# AFE_32.net
KiCad netlist of a schematic drawn in Altium Designer
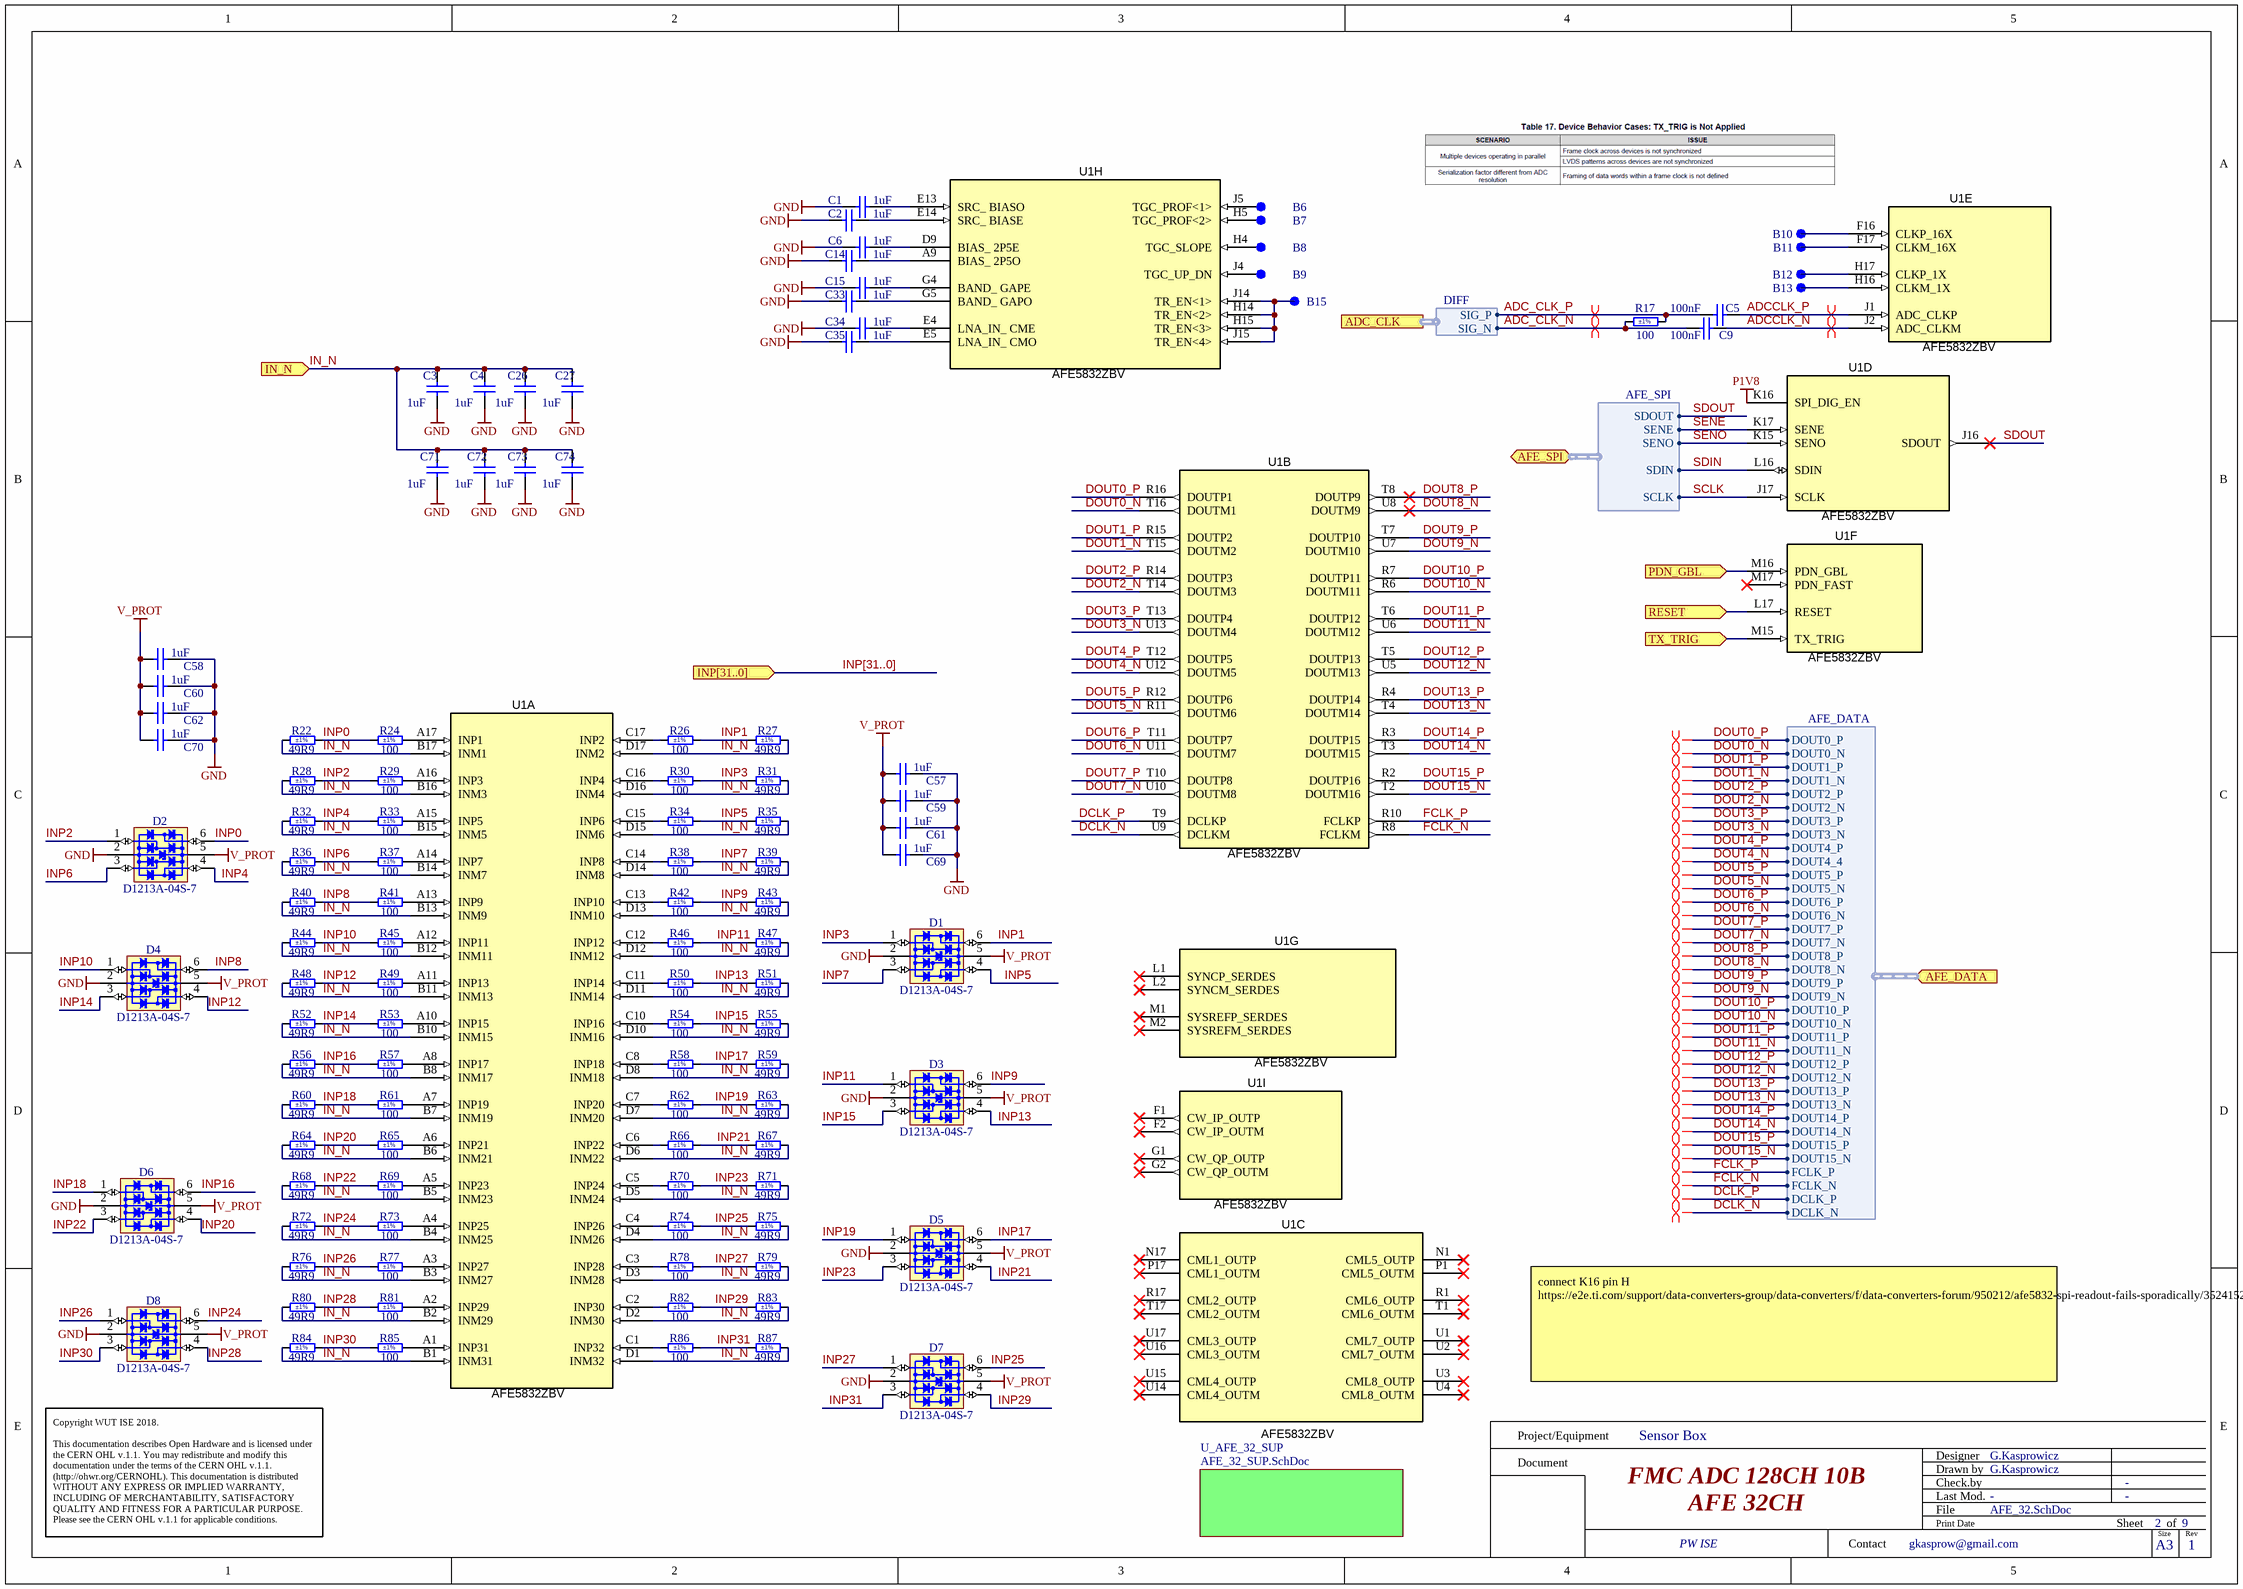
[diagram p0: AFE_32.SchDoc]

(export (version "E")
  (design (tool "Eeschema 10.0.6"))
  (components
    (comp (ref "B6")
      (value "SMD Pad")
      (footprint "C75")
      (description "Through Hole Pad")
      (fields (field (name "PART NUMBER") "SMD_PAD_D0.75MM") (field (name "AUTHOR") "CERN DEM BC"))
      (libsource (lib "Eletro-mechanical") (part "Single SMD Pad (Round)"))
    )
    (comp (ref "B7")
      (value "SMD Pad")
      (footprint "C75")
      (description "Through Hole Pad")
      (fields (field (name "PART NUMBER") "SMD_PAD_D0.75MM") (field (name "AUTHOR") "CERN DEM BC"))
      (libsource (lib "Eletro-mechanical") (part "Single SMD Pad (Round)"))
    )
    (comp (ref "B8")
      (value "SMD Pad")
      (footprint "C75")
      (description "Through Hole Pad")
      (fields (field (name "PART NUMBER") "SMD_PAD_D0.75MM") (field (name "AUTHOR") "CERN DEM BC"))
      (libsource (lib "Eletro-mechanical") (part "Single SMD Pad (Round)"))
    )
    (comp (ref "B9")
      (value "SMD Pad")
      (footprint "C75")
      (description "Through Hole Pad")
      (fields (field (name "PART NUMBER") "SMD_PAD_D0.75MM") (field (name "AUTHOR") "CERN DEM BC"))
      (libsource (lib "Eletro-mechanical") (part "Single SMD Pad (Round)"))
    )
    (comp (ref "B10")
      (value "SMD Pad")
      (footprint "C75")
      (description "Through Hole Pad")
      (fields (field (name "PART NUMBER") "SMD_PAD_D0.75MM") (field (name "AUTHOR") "CERN DEM BC"))
      (libsource (lib "Eletro-mechanical") (part "Single SMD Pad (Round)"))
    )
    (comp (ref "B11")
      (value "SMD Pad")
      (footprint "C75")
      (description "Through Hole Pad")
      (fields (field (name "PART NUMBER") "SMD_PAD_D0.75MM") (field (name "AUTHOR") "CERN DEM BC"))
      (libsource (lib "Eletro-mechanical") (part "Single SMD Pad (Round)"))
    )
    (comp (ref "B12")
      (value "SMD Pad")
      (footprint "C75")
      (description "Through Hole Pad")
      (fields (field (name "PART NUMBER") "SMD_PAD_D0.75MM") (field (name "AUTHOR") "CERN DEM BC"))
      (libsource (lib "Eletro-mechanical") (part "Single SMD Pad (Round)"))
    )
    (comp (ref "B13")
      (value "SMD Pad")
      (footprint "C75")
      (description "Through Hole Pad")
      (fields (field (name "PART NUMBER") "SMD_PAD_D0.75MM") (field (name "AUTHOR") "CERN DEM BC"))
      (libsource (lib "Eletro-mechanical") (part "Single SMD Pad (Round)"))
    )
    (comp (ref "B15")
      (value "SMD Pad")
      (footprint "C75")
      (description "Through Hole Pad")
      (fields (field (name "PART NUMBER") "SMD_PAD_D0.75MM") (field (name "AUTHOR") "CERN DEM BC"))
      (libsource (lib "Eletro-mechanical") (part "Single SMD Pad (Round)"))
    )
    (comp (ref "C1")
      (value "1uF")
      (footprint "CAPC1005X55N")
      (description "Non-polarised capacitor")
      (fields
        (field (name "PART NUMBER") "CC0402_1UF_25V_10%_X5R")
        (field (name "VOLTAGE") "25V")
        (field (name "AUTHOR") "CERN DEM BC")
      )
      (libsource (lib "Capacitors") (part "Capacitor - non polarized"))
    )
    (comp (ref "C2")
      (value "1uF")
      (footprint "CAPC1005X55N")
      (description "Non-polarised capacitor")
      (fields
        (field (name "PART NUMBER") "CC0402_1UF_25V_10%_X5R")
        (field (name "VOLTAGE") "25V")
        (field (name "AUTHOR") "CERN DEM BC")
      )
      (libsource (lib "Capacitors") (part "Capacitor - non polarized"))
    )
    (comp (ref "C3")
      (value "1uF")
      (footprint "CAPC1005X55N")
      (description "Non-polarised capacitor")
      (fields
        (field (name "PART NUMBER") "CC0402_1UF_25V_10%_X5R")
        (field (name "VOLTAGE") "25V")
        (field (name "AUTHOR") "CERN DEM BC")
      )
      (libsource (lib "Capacitors") (part "Capacitor - non polarized"))
    )
    (comp (ref "C4")
      (value "1uF")
      (footprint "CAPC1005X55N")
      (description "Non-polarised capacitor")
      (fields
        (field (name "PART NUMBER") "CC0402_1UF_25V_10%_X5R")
        (field (name "VOLTAGE") "25V")
        (field (name "AUTHOR") "CERN DEM BC")
      )
      (libsource (lib "Capacitors") (part "Capacitor - non polarized"))
    )
    (comp (ref "C5")
      (value "100nF")
      (footprint "CAPC0603X33N")
      (description "Non-polarised capacitor")
      (fields
        (field (name "PART NUMBER") "CC0201_100NF_6.3V_10%_X5R")
        (field (name "VOLTAGE") "6.3V")
        (field (name "AUTHOR") "CERN DEM JLC")
      )
      (libsource (lib "Capacitors") (part "Capacitor - non polarized"))
    )
    (comp (ref "C6")
      (value "1uF")
      (footprint "CAPC1005X55N")
      (description "Non-polarised capacitor")
      (fields
        (field (name "PART NUMBER") "CC0402_1UF_25V_10%_X5R")
        (field (name "VOLTAGE") "25V")
        (field (name "AUTHOR") "CERN DEM BC")
      )
      (libsource (lib "Capacitors") (part "Capacitor - non polarized"))
    )
    (comp (ref "C9")
      (value "100nF")
      (footprint "CAPC0603X33N")
      (description "Non-polarised capacitor")
      (fields
        (field (name "PART NUMBER") "CC0201_100NF_6.3V_10%_X5R")
        (field (name "VOLTAGE") "6.3V")
        (field (name "AUTHOR") "CERN DEM JLC")
      )
      (libsource (lib "Capacitors") (part "Capacitor - non polarized"))
    )
    (comp (ref "C14")
      (value "1uF")
      (footprint "CAPC1005X55N")
      (description "Non-polarised capacitor")
      (fields
        (field (name "PART NUMBER") "CC0402_1UF_25V_10%_X5R")
        (field (name "VOLTAGE") "25V")
        (field (name "AUTHOR") "CERN DEM BC")
      )
      (libsource (lib "Capacitors") (part "Capacitor - non polarized"))
    )
    (comp (ref "C15")
      (value "1uF")
      (footprint "CAPC1005X55N")
      (description "Non-polarised capacitor")
      (fields
        (field (name "PART NUMBER") "CC0402_1UF_25V_10%_X5R")
        (field (name "VOLTAGE") "25V")
        (field (name "AUTHOR") "CERN DEM BC")
      )
      (libsource (lib "Capacitors") (part "Capacitor - non polarized"))
    )
    (comp (ref "C26")
      (value "1uF")
      (footprint "CAPC1005X55N")
      (description "Non-polarised capacitor")
      (fields
        (field (name "PART NUMBER") "CC0402_1UF_25V_10%_X5R")
        (field (name "VOLTAGE") "25V")
        (field (name "AUTHOR") "CERN DEM BC")
      )
      (libsource (lib "Capacitors") (part "Capacitor - non polarized"))
    )
    (comp (ref "C27")
      (value "1uF")
      (footprint "CAPC1005X55N")
      (description "Non-polarised capacitor")
      (fields
        (field (name "PART NUMBER") "CC0402_1UF_25V_10%_X5R")
        (field (name "VOLTAGE") "25V")
        (field (name "AUTHOR") "CERN DEM BC")
      )
      (libsource (lib "Capacitors") (part "Capacitor - non polarized"))
    )
    (comp (ref "C33")
      (value "1uF")
      (footprint "CAPC1005X55N")
      (description "Non-polarised capacitor")
      (fields
        (field (name "PART NUMBER") "CC0402_1UF_25V_10%_X5R")
        (field (name "VOLTAGE") "25V")
        (field (name "AUTHOR") "CERN DEM BC")
      )
      (libsource (lib "Capacitors") (part "Capacitor - non polarized"))
    )
    (comp (ref "C34")
      (value "1uF")
      (footprint "CAPC1005X55N")
      (description "Non-polarised capacitor")
      (fields
        (field (name "PART NUMBER") "CC0402_1UF_25V_10%_X5R")
        (field (name "VOLTAGE") "25V")
        (field (name "AUTHOR") "CERN DEM BC")
      )
      (libsource (lib "Capacitors") (part "Capacitor - non polarized"))
    )
    (comp (ref "C35")
      (value "1uF")
      (footprint "CAPC1005X55N")
      (description "Non-polarised capacitor")
      (fields
        (field (name "PART NUMBER") "CC0402_1UF_25V_10%_X5R")
        (field (name "VOLTAGE") "25V")
        (field (name "AUTHOR") "CERN DEM BC")
      )
      (libsource (lib "Capacitors") (part "Capacitor - non polarized"))
    )
    (comp (ref "C57")
      (value "1uF")
      (footprint "CAPC1005X55N")
      (description "Non-polarised capacitor")
      (fields
        (field (name "PART NUMBER") "CC0402_1UF_25V_10%_X5R")
        (field (name "VOLTAGE") "25V")
        (field (name "AUTHOR") "CERN DEM BC")
      )
      (libsource (lib "Capacitors") (part "Capacitor - non polarized"))
    )
    (comp (ref "C58")
      (value "1uF")
      (footprint "CAPC1005X55N")
      (description "Non-polarised capacitor")
      (fields
        (field (name "PART NUMBER") "CC0402_1UF_25V_10%_X5R")
        (field (name "VOLTAGE") "25V")
        (field (name "AUTHOR") "CERN DEM BC")
      )
      (libsource (lib "Capacitors") (part "Capacitor - non polarized"))
    )
    (comp (ref "C59")
      (value "1uF")
      (footprint "CAPC1005X55N")
      (description "Non-polarised capacitor")
      (fields
        (field (name "PART NUMBER") "CC0402_1UF_25V_10%_X5R")
        (field (name "VOLTAGE") "25V")
        (field (name "AUTHOR") "CERN DEM BC")
      )
      (libsource (lib "Capacitors") (part "Capacitor - non polarized"))
    )
    (comp (ref "C60")
      (value "1uF")
      (footprint "CAPC1005X55N")
      (description "Non-polarised capacitor")
      (fields
        (field (name "PART NUMBER") "CC0402_1UF_25V_10%_X5R")
        (field (name "VOLTAGE") "25V")
        (field (name "AUTHOR") "CERN DEM BC")
      )
      (libsource (lib "Capacitors") (part "Capacitor - non polarized"))
    )
    (comp (ref "C61")
      (value "1uF")
      (footprint "CAPC1005X55N")
      (description "Non-polarised capacitor")
      (fields
        (field (name "PART NUMBER") "CC0402_1UF_25V_10%_X5R")
        (field (name "VOLTAGE") "25V")
        (field (name "AUTHOR") "CERN DEM BC")
      )
      (libsource (lib "Capacitors") (part "Capacitor - non polarized"))
    )
    (comp (ref "C62")
      (value "1uF")
      (footprint "CAPC1005X55N")
      (description "Non-polarised capacitor")
      (fields
        (field (name "PART NUMBER") "CC0402_1UF_25V_10%_X5R")
        (field (name "VOLTAGE") "25V")
        (field (name "AUTHOR") "CERN DEM BC")
      )
      (libsource (lib "Capacitors") (part "Capacitor - non polarized"))
    )
    (comp (ref "C69")
      (value "1uF")
      (footprint "CAPC1005X55N")
      (description "Non-polarised capacitor")
      (fields
        (field (name "PART NUMBER") "CC0402_1UF_25V_10%_X5R")
        (field (name "VOLTAGE") "25V")
        (field (name "AUTHOR") "CERN DEM BC")
      )
      (libsource (lib "Capacitors") (part "Capacitor - non polarized"))
    )
    (comp (ref "C70")
      (value "1uF")
      (footprint "CAPC1005X55N")
      (description "Non-polarised capacitor")
      (fields
        (field (name "PART NUMBER") "CC0402_1UF_25V_10%_X5R")
        (field (name "VOLTAGE") "25V")
        (field (name "AUTHOR") "CERN DEM BC")
      )
      (libsource (lib "Capacitors") (part "Capacitor - non polarized"))
    )
    (comp (ref "C71")
      (value "1uF")
      (footprint "CAPC1005X55N")
      (description "Non-polarised capacitor")
      (fields
        (field (name "PART NUMBER") "CC0402_1UF_25V_10%_X5R")
        (field (name "VOLTAGE") "25V")
        (field (name "AUTHOR") "CERN DEM BC")
      )
      (libsource (lib "Capacitors") (part "Capacitor - non polarized"))
    )
    (comp (ref "C72")
      (value "1uF")
      (footprint "CAPC1005X55N")
      (description "Non-polarised capacitor")
      (fields
        (field (name "PART NUMBER") "CC0402_1UF_25V_10%_X5R")
        (field (name "VOLTAGE") "25V")
        (field (name "AUTHOR") "CERN DEM BC")
      )
      (libsource (lib "Capacitors") (part "Capacitor - non polarized"))
    )
    (comp (ref "C73")
      (value "1uF")
      (footprint "CAPC1005X55N")
      (description "Non-polarised capacitor")
      (fields
        (field (name "PART NUMBER") "CC0402_1UF_25V_10%_X5R")
        (field (name "VOLTAGE") "25V")
        (field (name "AUTHOR") "CERN DEM BC")
      )
      (libsource (lib "Capacitors") (part "Capacitor - non polarized"))
    )
    (comp (ref "C74")
      (value "1uF")
      (footprint "CAPC1005X55N")
      (description "Non-polarised capacitor")
      (fields
        (field (name "PART NUMBER") "CC0402_1UF_25V_10%_X5R")
        (field (name "VOLTAGE") "25V")
        (field (name "AUTHOR") "CERN DEM BC")
      )
      (libsource (lib "Capacitors") (part "Capacitor - non polarized"))
    )
    (comp (ref "D1")
      (value "D1213A-04S-7")
      (footprint "SOT65P210X110-6N")
      (description "Integrated Quad Ultra-Low Capacitance ESD Protection")
      (fields (field (name "MANUFACTURER") "DIODES") (field (name "AUTHOR") "GK"))
      (libsource (lib "Diodes") (part "D_TVS_D1213A-04S-7"))
    )
    (comp (ref "D2")
      (value "D1213A-04S-7")
      (footprint "SOT65P210X110-6N")
      (description "Integrated Quad Ultra-Low Capacitance ESD Protection")
      (fields (field (name "MANUFACTURER") "DIODES") (field (name "AUTHOR") "GK"))
      (libsource (lib "Diodes") (part "D_TVS_D1213A-04S-7"))
    )
    (comp (ref "D3")
      (value "D1213A-04S-7")
      (footprint "SOT65P210X110-6N")
      (description "Integrated Quad Ultra-Low Capacitance ESD Protection")
      (fields (field (name "MANUFACTURER") "DIODES") (field (name "AUTHOR") "GK"))
      (libsource (lib "Diodes") (part "D_TVS_D1213A-04S-7"))
    )
    (comp (ref "D4")
      (value "D1213A-04S-7")
      (footprint "SOT65P210X110-6N")
      (description "Integrated Quad Ultra-Low Capacitance ESD Protection")
      (fields (field (name "MANUFACTURER") "DIODES") (field (name "AUTHOR") "GK"))
      (libsource (lib "Diodes") (part "D_TVS_D1213A-04S-7"))
    )
    (comp (ref "D5")
      (value "D1213A-04S-7")
      (footprint "SOT65P210X110-6N")
      (description "Integrated Quad Ultra-Low Capacitance ESD Protection")
      (fields (field (name "MANUFACTURER") "DIODES") (field (name "AUTHOR") "GK"))
      (libsource (lib "Diodes") (part "D_TVS_D1213A-04S-7"))
    )
    (comp (ref "D6")
      (value "D1213A-04S-7")
      (footprint "SOT65P210X110-6N")
      (description "Integrated Quad Ultra-Low Capacitance ESD Protection")
      (fields (field (name "MANUFACTURER") "DIODES") (field (name "AUTHOR") "GK"))
      (libsource (lib "Diodes") (part "D_TVS_D1213A-04S-7"))
    )
    (comp (ref "D7")
      (value "D1213A-04S-7")
      (footprint "SOT65P210X110-6N")
      (description "Integrated Quad Ultra-Low Capacitance ESD Protection")
      (fields (field (name "MANUFACTURER") "DIODES") (field (name "AUTHOR") "GK"))
      (libsource (lib "Diodes") (part "D_TVS_D1213A-04S-7"))
    )
    (comp (ref "D8")
      (value "D1213A-04S-7")
      (footprint "SOT65P210X110-6N")
      (description "Integrated Quad Ultra-Low Capacitance ESD Protection")
      (fields (field (name "MANUFACTURER") "DIODES") (field (name "AUTHOR") "GK"))
      (libsource (lib "Diodes") (part "D_TVS_D1213A-04S-7"))
    )
    (comp (ref "R17")
      (value "100")
      (footprint "RESC1005X40N")
      (description "Resistor - 1%")
      (fields
        (field (name "TOLERANCE") "±1%")
        (field (name "PART NUMBER") "R0402_100R_1%_0.0625W_100PPM")
        (field (name "POWER") "0.0625W")
        (field (name "AUTHOR") "CERN DEM JLC")
      )
      (libsource (lib "Resistors") (part "Resistor - 1%"))
    )
    (comp (ref "R22")
      (value "49R9")
      (footprint "RESC0603X28N")
      (description "Resistor - 1%")
      (fields
        (field (name "TOLERANCE") "±1%")
        (field (name "PART NUMBER") "R0201_49R9_1%_0.05W_200PPM")
        (field (name "POWER") "0.05W")
        (field (name "AUTHOR") "CERN DEM BC")
      )
      (libsource (lib "Resistors") (part "Resistor - 1%"))
    )
    (comp (ref "R24")
      (value "100")
      (footprint "RESC0603X28N")
      (description "Resistor - 1%")
      (fields
        (field (name "TOLERANCE") "±1%")
        (field (name "PART NUMBER") "R0201_100R_1%_0.05W_200PPM")
        (field (name "POWER") "0.05W")
        (field (name "AUTHOR") "CERN DEM JLC")
      )
      (libsource (lib "Resistors") (part "Resistor - 1%"))
    )
    (comp (ref "R26")
      (value "100")
      (footprint "RESC0603X28N")
      (description "Resistor - 1%")
      (fields
        (field (name "TOLERANCE") "±1%")
        (field (name "PART NUMBER") "R0201_100R_1%_0.05W_200PPM")
        (field (name "POWER") "0.05W")
        (field (name "AUTHOR") "CERN DEM JLC")
      )
      (libsource (lib "Resistors") (part "Resistor - 1%"))
    )
    (comp (ref "R27")
      (value "49R9")
      (footprint "RESC0603X28N")
      (description "Resistor - 1%")
      (fields
        (field (name "TOLERANCE") "±1%")
        (field (name "PART NUMBER") "R0201_49R9_1%_0.05W_200PPM")
        (field (name "POWER") "0.05W")
        (field (name "AUTHOR") "CERN DEM BC")
      )
      (libsource (lib "Resistors") (part "Resistor - 1%"))
    )
    (comp (ref "R28")
      (value "49R9")
      (footprint "RESC0603X28N")
      (description "Resistor - 1%")
      (fields
        (field (name "TOLERANCE") "±1%")
        (field (name "PART NUMBER") "R0201_49R9_1%_0.05W_200PPM")
        (field (name "POWER") "0.05W")
        (field (name "AUTHOR") "CERN DEM BC")
      )
      (libsource (lib "Resistors") (part "Resistor - 1%"))
    )
    (comp (ref "R29")
      (value "100")
      (footprint "RESC0603X28N")
      (description "Resistor - 1%")
      (fields
        (field (name "TOLERANCE") "±1%")
        (field (name "PART NUMBER") "R0201_100R_1%_0.05W_200PPM")
        (field (name "POWER") "0.05W")
        (field (name "AUTHOR") "CERN DEM JLC")
      )
      (libsource (lib "Resistors") (part "Resistor - 1%"))
    )
    (comp (ref "R30")
      (value "100")
      (footprint "RESC0603X28N")
      (description "Resistor - 1%")
      (fields
        (field (name "TOLERANCE") "±1%")
        (field (name "PART NUMBER") "R0201_100R_1%_0.05W_200PPM")
        (field (name "POWER") "0.05W")
        (field (name "AUTHOR") "CERN DEM JLC")
      )
      (libsource (lib "Resistors") (part "Resistor - 1%"))
    )
    (comp (ref "R31")
      (value "49R9")
      (footprint "RESC0603X28N")
      (description "Resistor - 1%")
      (fields
        (field (name "TOLERANCE") "±1%")
        (field (name "PART NUMBER") "R0201_49R9_1%_0.05W_200PPM")
        (field (name "POWER") "0.05W")
        (field (name "AUTHOR") "CERN DEM BC")
      )
      (libsource (lib "Resistors") (part "Resistor - 1%"))
    )
    (comp (ref "R32")
      (value "49R9")
      (footprint "RESC0603X28N")
      (description "Resistor - 1%")
      (fields
        (field (name "TOLERANCE") "±1%")
        (field (name "PART NUMBER") "R0201_49R9_1%_0.05W_200PPM")
        (field (name "POWER") "0.05W")
        (field (name "AUTHOR") "CERN DEM BC")
      )
      (libsource (lib "Resistors") (part "Resistor - 1%"))
    )
    (comp (ref "R33")
      (value "100")
      (footprint "RESC0603X28N")
      (description "Resistor - 1%")
      (fields
        (field (name "TOLERANCE") "±1%")
        (field (name "PART NUMBER") "R0201_100R_1%_0.05W_200PPM")
        (field (name "POWER") "0.05W")
        (field (name "AUTHOR") "CERN DEM JLC")
      )
      (libsource (lib "Resistors") (part "Resistor - 1%"))
    )
    (comp (ref "R34")
      (value "100")
      (footprint "RESC0603X28N")
      (description "Resistor - 1%")
      (fields
        (field (name "TOLERANCE") "±1%")
        (field (name "PART NUMBER") "R0201_100R_1%_0.05W_200PPM")
        (field (name "POWER") "0.05W")
        (field (name "AUTHOR") "CERN DEM JLC")
      )
      (libsource (lib "Resistors") (part "Resistor - 1%"))
    )
    (comp (ref "R35")
      (value "49R9")
      (footprint "RESC0603X28N")
      (description "Resistor - 1%")
      (fields
        (field (name "TOLERANCE") "±1%")
        (field (name "PART NUMBER") "R0201_49R9_1%_0.05W_200PPM")
        (field (name "POWER") "0.05W")
        (field (name "AUTHOR") "CERN DEM BC")
      )
      (libsource (lib "Resistors") (part "Resistor - 1%"))
    )
    (comp (ref "R36")
      (value "49R9")
      (footprint "RESC0603X28N")
      (description "Resistor - 1%")
      (fields
        (field (name "TOLERANCE") "±1%")
        (field (name "PART NUMBER") "R0201_49R9_1%_0.05W_200PPM")
        (field (name "POWER") "0.05W")
        (field (name "AUTHOR") "CERN DEM BC")
      )
      (libsource (lib "Resistors") (part "Resistor - 1%"))
    )
    (comp (ref "R37")
      (value "100")
      (footprint "RESC0603X28N")
      (description "Resistor - 1%")
      (fields
        (field (name "TOLERANCE") "±1%")
        (field (name "PART NUMBER") "R0201_100R_1%_0.05W_200PPM")
        (field (name "POWER") "0.05W")
        (field (name "AUTHOR") "CERN DEM JLC")
      )
      (libsource (lib "Resistors") (part "Resistor - 1%"))
    )
    (comp (ref "R38")
      (value "100")
      (footprint "RESC0603X28N")
      (description "Resistor - 1%")
      (fields
        (field (name "TOLERANCE") "±1%")
        (field (name "PART NUMBER") "R0201_100R_1%_0.05W_200PPM")
        (field (name "POWER") "0.05W")
        (field (name "AUTHOR") "CERN DEM JLC")
      )
      (libsource (lib "Resistors") (part "Resistor - 1%"))
    )
    (comp (ref "R39")
      (value "49R9")
      (footprint "RESC0603X28N")
      (description "Resistor - 1%")
      (fields
        (field (name "TOLERANCE") "±1%")
        (field (name "PART NUMBER") "R0201_49R9_1%_0.05W_200PPM")
        (field (name "POWER") "0.05W")
        (field (name "AUTHOR") "CERN DEM BC")
      )
      (libsource (lib "Resistors") (part "Resistor - 1%"))
    )
    (comp (ref "R40")
      (value "49R9")
      (footprint "RESC0603X28N")
      (description "Resistor - 1%")
      (fields
        (field (name "TOLERANCE") "±1%")
        (field (name "PART NUMBER") "R0201_49R9_1%_0.05W_200PPM")
        (field (name "POWER") "0.05W")
        (field (name "AUTHOR") "CERN DEM BC")
      )
      (libsource (lib "Resistors") (part "Resistor - 1%"))
    )
    (comp (ref "R41")
      (value "100")
      (footprint "RESC0603X28N")
      (description "Resistor - 1%")
      (fields
        (field (name "TOLERANCE") "±1%")
        (field (name "PART NUMBER") "R0201_100R_1%_0.05W_200PPM")
        (field (name "POWER") "0.05W")
        (field (name "AUTHOR") "CERN DEM JLC")
      )
      (libsource (lib "Resistors") (part "Resistor - 1%"))
    )
    (comp (ref "R42")
      (value "100")
      (footprint "RESC0603X28N")
      (description "Resistor - 1%")
      (fields
        (field (name "TOLERANCE") "±1%")
        (field (name "PART NUMBER") "R0201_100R_1%_0.05W_200PPM")
        (field (name "POWER") "0.05W")
        (field (name "AUTHOR") "CERN DEM JLC")
      )
      (libsource (lib "Resistors") (part "Resistor - 1%"))
    )
    (comp (ref "R43")
      (value "49R9")
      (footprint "RESC0603X28N")
      (description "Resistor - 1%")
      (fields
        (field (name "TOLERANCE") "±1%")
        (field (name "PART NUMBER") "R0201_49R9_1%_0.05W_200PPM")
        (field (name "POWER") "0.05W")
        (field (name "AUTHOR") "CERN DEM BC")
      )
      (libsource (lib "Resistors") (part "Resistor - 1%"))
    )
    (comp (ref "R44")
      (value "49R9")
      (footprint "RESC0603X28N")
      (description "Resistor - 1%")
      (fields
        (field (name "TOLERANCE") "±1%")
        (field (name "PART NUMBER") "R0201_49R9_1%_0.05W_200PPM")
        (field (name "POWER") "0.05W")
        (field (name "AUTHOR") "CERN DEM BC")
      )
      (libsource (lib "Resistors") (part "Resistor - 1%"))
    )
    (comp (ref "R45")
      (value "100")
      (footprint "RESC0603X28N")
      (description "Resistor - 1%")
      (fields
        (field (name "TOLERANCE") "±1%")
        (field (name "PART NUMBER") "R0201_100R_1%_0.05W_200PPM")
        (field (name "POWER") "0.05W")
        (field (name "AUTHOR") "CERN DEM JLC")
      )
      (libsource (lib "Resistors") (part "Resistor - 1%"))
    )
    (comp (ref "R46")
      (value "100")
      (footprint "RESC0603X28N")
      (description "Resistor - 1%")
      (fields
        (field (name "TOLERANCE") "±1%")
        (field (name "PART NUMBER") "R0201_100R_1%_0.05W_200PPM")
        (field (name "POWER") "0.05W")
        (field (name "AUTHOR") "CERN DEM JLC")
      )
      (libsource (lib "Resistors") (part "Resistor - 1%"))
    )
    (comp (ref "R47")
      (value "49R9")
      (footprint "RESC0603X28N")
      (description "Resistor - 1%")
      (fields
        (field (name "TOLERANCE") "±1%")
        (field (name "PART NUMBER") "R0201_49R9_1%_0.05W_200PPM")
        (field (name "POWER") "0.05W")
        (field (name "AUTHOR") "CERN DEM BC")
      )
      (libsource (lib "Resistors") (part "Resistor - 1%"))
    )
    (comp (ref "R48")
      (value "49R9")
      (footprint "RESC0603X28N")
      (description "Resistor - 1%")
      (fields
        (field (name "TOLERANCE") "±1%")
        (field (name "PART NUMBER") "R0201_49R9_1%_0.05W_200PPM")
        (field (name "POWER") "0.05W")
        (field (name "AUTHOR") "CERN DEM BC")
      )
      (libsource (lib "Resistors") (part "Resistor - 1%"))
    )
    (comp (ref "R49")
      (value "100")
      (footprint "RESC0603X28N")
      (description "Resistor - 1%")
      (fields
        (field (name "TOLERANCE") "±1%")
        (field (name "PART NUMBER") "R0201_100R_1%_0.05W_200PPM")
        (field (name "POWER") "0.05W")
        (field (name "AUTHOR") "CERN DEM JLC")
      )
      (libsource (lib "Resistors") (part "Resistor - 1%"))
    )
    (comp (ref "R50")
      (value "100")
      (footprint "RESC0603X28N")
      (description "Resistor - 1%")
      (fields
        (field (name "TOLERANCE") "±1%")
        (field (name "PART NUMBER") "R0201_100R_1%_0.05W_200PPM")
        (field (name "POWER") "0.05W")
        (field (name "AUTHOR") "CERN DEM JLC")
      )
      (libsource (lib "Resistors") (part "Resistor - 1%"))
    )
    (comp (ref "R51")
      (value "49R9")
      (footprint "RESC0603X28N")
      (description "Resistor - 1%")
      (fields
        (field (name "TOLERANCE") "±1%")
        (field (name "PART NUMBER") "R0201_49R9_1%_0.05W_200PPM")
        (field (name "POWER") "0.05W")
        (field (name "AUTHOR") "CERN DEM BC")
      )
      (libsource (lib "Resistors") (part "Resistor - 1%"))
    )
    (comp (ref "R52")
      (value "49R9")
      (footprint "RESC0603X28N")
      (description "Resistor - 1%")
      (fields
        (field (name "TOLERANCE") "±1%")
        (field (name "PART NUMBER") "R0201_49R9_1%_0.05W_200PPM")
        (field (name "POWER") "0.05W")
        (field (name "AUTHOR") "CERN DEM BC")
      )
      (libsource (lib "Resistors") (part "Resistor - 1%"))
    )
    (comp (ref "R53")
      (value "100")
      (footprint "RESC0603X28N")
      (description "Resistor - 1%")
      (fields
        (field (name "TOLERANCE") "±1%")
        (field (name "PART NUMBER") "R0201_100R_1%_0.05W_200PPM")
        (field (name "POWER") "0.05W")
        (field (name "AUTHOR") "CERN DEM JLC")
      )
      (libsource (lib "Resistors") (part "Resistor - 1%"))
    )
    (comp (ref "R54")
      (value "100")
      (footprint "RESC0603X28N")
      (description "Resistor - 1%")
      (fields
        (field (name "TOLERANCE") "±1%")
        (field (name "PART NUMBER") "R0201_100R_1%_0.05W_200PPM")
        (field (name "POWER") "0.05W")
        (field (name "AUTHOR") "CERN DEM JLC")
      )
      (libsource (lib "Resistors") (part "Resistor - 1%"))
    )
    (comp (ref "R55")
      (value "49R9")
      (footprint "RESC0603X28N")
      (description "Resistor - 1%")
      (fields
        (field (name "TOLERANCE") "±1%")
        (field (name "PART NUMBER") "R0201_49R9_1%_0.05W_200PPM")
        (field (name "POWER") "0.05W")
        (field (name "AUTHOR") "CERN DEM BC")
      )
      (libsource (lib "Resistors") (part "Resistor - 1%"))
    )
    (comp (ref "R56")
      (value "49R9")
      (footprint "RESC0603X28N")
      (description "Resistor - 1%")
      (fields
        (field (name "TOLERANCE") "±1%")
        (field (name "PART NUMBER") "R0201_49R9_1%_0.05W_200PPM")
        (field (name "POWER") "0.05W")
        (field (name "AUTHOR") "CERN DEM BC")
      )
      (libsource (lib "Resistors") (part "Resistor - 1%"))
    )
    (comp (ref "R57")
      (value "100")
      (footprint "RESC0603X28N")
      (description "Resistor - 1%")
      (fields
        (field (name "TOLERANCE") "±1%")
        (field (name "PART NUMBER") "R0201_100R_1%_0.05W_200PPM")
        (field (name "POWER") "0.05W")
        (field (name "AUTHOR") "CERN DEM JLC")
      )
      (libsource (lib "Resistors") (part "Resistor - 1%"))
    )
    (comp (ref "R58")
      (value "100")
      (footprint "RESC0603X28N")
      (description "Resistor - 1%")
      (fields
        (field (name "TOLERANCE") "±1%")
        (field (name "PART NUMBER") "R0201_100R_1%_0.05W_200PPM")
        (field (name "POWER") "0.05W")
        (field (name "AUTHOR") "CERN DEM JLC")
      )
      (libsource (lib "Resistors") (part "Resistor - 1%"))
    )
    (comp (ref "R59")
      (value "49R9")
      (footprint "RESC0603X28N")
      (description "Resistor - 1%")
      (fields
        (field (name "TOLERANCE") "±1%")
        (field (name "PART NUMBER") "R0201_49R9_1%_0.05W_200PPM")
        (field (name "POWER") "0.05W")
        (field (name "AUTHOR") "CERN DEM BC")
      )
      (libsource (lib "Resistors") (part "Resistor - 1%"))
    )
    (comp (ref "R60")
      (value "49R9")
      (footprint "RESC0603X28N")
      (description "Resistor - 1%")
      (fields
        (field (name "TOLERANCE") "±1%")
        (field (name "PART NUMBER") "R0201_49R9_1%_0.05W_200PPM")
        (field (name "POWER") "0.05W")
        (field (name "AUTHOR") "CERN DEM BC")
      )
      (libsource (lib "Resistors") (part "Resistor - 1%"))
    )
    (comp (ref "R61")
      (value "100")
      (footprint "RESC0603X28N")
      (description "Resistor - 1%")
      (fields
        (field (name "TOLERANCE") "±1%")
        (field (name "PART NUMBER") "R0201_100R_1%_0.05W_200PPM")
        (field (name "POWER") "0.05W")
        (field (name "AUTHOR") "CERN DEM JLC")
      )
      (libsource (lib "Resistors") (part "Resistor - 1%"))
    )
    (comp (ref "R62")
      (value "100")
      (footprint "RESC0603X28N")
      (description "Resistor - 1%")
      (fields
        (field (name "TOLERANCE") "±1%")
        (field (name "PART NUMBER") "R0201_100R_1%_0.05W_200PPM")
        (field (name "POWER") "0.05W")
        (field (name "AUTHOR") "CERN DEM JLC")
      )
      (libsource (lib "Resistors") (part "Resistor - 1%"))
    )
    (comp (ref "R63")
      (value "49R9")
      (footprint "RESC0603X28N")
      (description "Resistor - 1%")
      (fields
        (field (name "TOLERANCE") "±1%")
        (field (name "PART NUMBER") "R0201_49R9_1%_0.05W_200PPM")
        (field (name "POWER") "0.05W")
        (field (name "AUTHOR") "CERN DEM BC")
      )
      (libsource (lib "Resistors") (part "Resistor - 1%"))
    )
    (comp (ref "R64")
      (value "49R9")
      (footprint "RESC0603X28N")
      (description "Resistor - 1%")
      (fields
        (field (name "TOLERANCE") "±1%")
        (field (name "PART NUMBER") "R0201_49R9_1%_0.05W_200PPM")
        (field (name "POWER") "0.05W")
        (field (name "AUTHOR") "CERN DEM BC")
      )
      (libsource (lib "Resistors") (part "Resistor - 1%"))
    )
    (comp (ref "R65")
      (value "100")
      (footprint "RESC0603X28N")
      (description "Resistor - 1%")
      (fields
        (field (name "TOLERANCE") "±1%")
        (field (name "PART NUMBER") "R0201_100R_1%_0.05W_200PPM")
        (field (name "POWER") "0.05W")
        (field (name "AUTHOR") "CERN DEM JLC")
      )
      (libsource (lib "Resistors") (part "Resistor - 1%"))
    )
    (comp (ref "R66")
      (value "100")
      (footprint "RESC0603X28N")
      (description "Resistor - 1%")
      (fields
        (field (name "TOLERANCE") "±1%")
        (field (name "PART NUMBER") "R0201_100R_1%_0.05W_200PPM")
        (field (name "POWER") "0.05W")
        (field (name "AUTHOR") "CERN DEM JLC")
      )
      (libsource (lib "Resistors") (part "Resistor - 1%"))
    )
    (comp (ref "R67")
      (value "49R9")
      (footprint "RESC0603X28N")
      (description "Resistor - 1%")
      (fields
        (field (name "TOLERANCE") "±1%")
        (field (name "PART NUMBER") "R0201_49R9_1%_0.05W_200PPM")
        (field (name "POWER") "0.05W")
        (field (name "AUTHOR") "CERN DEM BC")
      )
      (libsource (lib "Resistors") (part "Resistor - 1%"))
    )
    (comp (ref "R68")
      (value "49R9")
      (footprint "RESC0603X28N")
      (description "Resistor - 1%")
      (fields
        (field (name "TOLERANCE") "±1%")
        (field (name "PART NUMBER") "R0201_49R9_1%_0.05W_200PPM")
        (field (name "POWER") "0.05W")
        (field (name "AUTHOR") "CERN DEM BC")
      )
      (libsource (lib "Resistors") (part "Resistor - 1%"))
    )
    (comp (ref "R69")
      (value "100")
      (footprint "RESC0603X28N")
      (description "Resistor - 1%")
      (fields
        (field (name "TOLERANCE") "±1%")
        (field (name "PART NUMBER") "R0201_100R_1%_0.05W_200PPM")
        (field (name "POWER") "0.05W")
        (field (name "AUTHOR") "CERN DEM JLC")
      )
      (libsource (lib "Resistors") (part "Resistor - 1%"))
    )
    (comp (ref "R70")
      (value "100")
      (footprint "RESC0603X28N")
      (description "Resistor - 1%")
      (fields
        (field (name "TOLERANCE") "±1%")
        (field (name "PART NUMBER") "R0201_100R_1%_0.05W_200PPM")
        (field (name "POWER") "0.05W")
        (field (name "AUTHOR") "CERN DEM JLC")
      )
      (libsource (lib "Resistors") (part "Resistor - 1%"))
    )
    (comp (ref "R71")
      (value "49R9")
      (footprint "RESC0603X28N")
      (description "Resistor - 1%")
      (fields
        (field (name "TOLERANCE") "±1%")
        (field (name "PART NUMBER") "R0201_49R9_1%_0.05W_200PPM")
        (field (name "POWER") "0.05W")
        (field (name "AUTHOR") "CERN DEM BC")
      )
      (libsource (lib "Resistors") (part "Resistor - 1%"))
    )
    (comp (ref "R72")
      (value "49R9")
      (footprint "RESC0603X28N")
      (description "Resistor - 1%")
      (fields
        (field (name "TOLERANCE") "±1%")
        (field (name "PART NUMBER") "R0201_49R9_1%_0.05W_200PPM")
        (field (name "POWER") "0.05W")
        (field (name "AUTHOR") "CERN DEM BC")
      )
      (libsource (lib "Resistors") (part "Resistor - 1%"))
    )
    (comp (ref "R73")
      (value "100")
      (footprint "RESC0603X28N")
      (description "Resistor - 1%")
      (fields
        (field (name "TOLERANCE") "±1%")
        (field (name "PART NUMBER") "R0201_100R_1%_0.05W_200PPM")
        (field (name "POWER") "0.05W")
        (field (name "AUTHOR") "CERN DEM JLC")
      )
      (libsource (lib "Resistors") (part "Resistor - 1%"))
    )
    (comp (ref "R74")
      (value "100")
      (footprint "RESC0603X28N")
      (description "Resistor - 1%")
      (fields
        (field (name "TOLERANCE") "±1%")
        (field (name "PART NUMBER") "R0201_100R_1%_0.05W_200PPM")
        (field (name "POWER") "0.05W")
        (field (name "AUTHOR") "CERN DEM JLC")
      )
      (libsource (lib "Resistors") (part "Resistor - 1%"))
    )
    (comp (ref "R75")
      (value "49R9")
      (footprint "RESC0603X28N")
      (description "Resistor - 1%")
      (fields
        (field (name "TOLERANCE") "±1%")
        (field (name "PART NUMBER") "R0201_49R9_1%_0.05W_200PPM")
        (field (name "POWER") "0.05W")
        (field (name "AUTHOR") "CERN DEM BC")
      )
      (libsource (lib "Resistors") (part "Resistor - 1%"))
    )
    (comp (ref "R76")
      (value "49R9")
      (footprint "RESC0603X28N")
      (description "Resistor - 1%")
      (fields
        (field (name "TOLERANCE") "±1%")
        (field (name "PART NUMBER") "R0201_49R9_1%_0.05W_200PPM")
        (field (name "POWER") "0.05W")
        (field (name "AUTHOR") "CERN DEM BC")
      )
      (libsource (lib "Resistors") (part "Resistor - 1%"))
    )
    (comp (ref "R77")
      (value "100")
      (footprint "RESC0603X28N")
      (description "Resistor - 1%")
      (fields
        (field (name "TOLERANCE") "±1%")
        (field (name "PART NUMBER") "R0201_100R_1%_0.05W_200PPM")
        (field (name "POWER") "0.05W")
        (field (name "AUTHOR") "CERN DEM JLC")
      )
      (libsource (lib "Resistors") (part "Resistor - 1%"))
    )
    (comp (ref "R78")
      (value "100")
      (footprint "RESC0603X28N")
      (description "Resistor - 1%")
      (fields
        (field (name "TOLERANCE") "±1%")
        (field (name "PART NUMBER") "R0201_100R_1%_0.05W_200PPM")
        (field (name "POWER") "0.05W")
        (field (name "AUTHOR") "CERN DEM JLC")
      )
      (libsource (lib "Resistors") (part "Resistor - 1%"))
    )
    (comp (ref "R79")
      (value "49R9")
      (footprint "RESC0603X28N")
      (description "Resistor - 1%")
      (fields
        (field (name "TOLERANCE") "±1%")
        (field (name "PART NUMBER") "R0201_49R9_1%_0.05W_200PPM")
        (field (name "POWER") "0.05W")
        (field (name "AUTHOR") "CERN DEM BC")
      )
      (libsource (lib "Resistors") (part "Resistor - 1%"))
    )
    (comp (ref "R80")
      (value "49R9")
      (footprint "RESC0603X28N")
      (description "Resistor - 1%")
      (fields
        (field (name "TOLERANCE") "±1%")
        (field (name "PART NUMBER") "R0201_49R9_1%_0.05W_200PPM")
        (field (name "POWER") "0.05W")
        (field (name "AUTHOR") "CERN DEM BC")
      )
      (libsource (lib "Resistors") (part "Resistor - 1%"))
    )
    (comp (ref "R81")
      (value "100")
      (footprint "RESC0603X28N")
      (description "Resistor - 1%")
      (fields
        (field (name "TOLERANCE") "±1%")
        (field (name "PART NUMBER") "R0201_100R_1%_0.05W_200PPM")
        (field (name "POWER") "0.05W")
        (field (name "AUTHOR") "CERN DEM JLC")
      )
      (libsource (lib "Resistors") (part "Resistor - 1%"))
    )
    (comp (ref "R82")
      (value "100")
      (footprint "RESC0603X28N")
      (description "Resistor - 1%")
      (fields
        (field (name "TOLERANCE") "±1%")
        (field (name "PART NUMBER") "R0201_100R_1%_0.05W_200PPM")
        (field (name "POWER") "0.05W")
        (field (name "AUTHOR") "CERN DEM JLC")
      )
      (libsource (lib "Resistors") (part "Resistor - 1%"))
    )
    (comp (ref "R83")
      (value "49R9")
      (footprint "RESC0603X28N")
      (description "Resistor - 1%")
      (fields
        (field (name "TOLERANCE") "±1%")
        (field (name "PART NUMBER") "R0201_49R9_1%_0.05W_200PPM")
        (field (name "POWER") "0.05W")
        (field (name "AUTHOR") "CERN DEM BC")
      )
      (libsource (lib "Resistors") (part "Resistor - 1%"))
    )
    (comp (ref "R84")
      (value "49R9")
      (footprint "RESC0603X28N")
      (description "Resistor - 1%")
      (fields
        (field (name "TOLERANCE") "±1%")
        (field (name "PART NUMBER") "R0201_49R9_1%_0.05W_200PPM")
        (field (name "POWER") "0.05W")
        (field (name "AUTHOR") "CERN DEM BC")
      )
      (libsource (lib "Resistors") (part "Resistor - 1%"))
    )
    (comp (ref "R85")
      (value "100")
      (footprint "RESC0603X28N")
      (description "Resistor - 1%")
      (fields
        (field (name "TOLERANCE") "±1%")
        (field (name "PART NUMBER") "R0201_100R_1%_0.05W_200PPM")
        (field (name "POWER") "0.05W")
        (field (name "AUTHOR") "CERN DEM JLC")
      )
      (libsource (lib "Resistors") (part "Resistor - 1%"))
    )
    (comp (ref "R86")
      (value "100")
      (footprint "RESC0603X28N")
      (description "Resistor - 1%")
      (fields
        (field (name "TOLERANCE") "±1%")
        (field (name "PART NUMBER") "R0201_100R_1%_0.05W_200PPM")
        (field (name "POWER") "0.05W")
        (field (name "AUTHOR") "CERN DEM JLC")
      )
      (libsource (lib "Resistors") (part "Resistor - 1%"))
    )
    (comp (ref "R87")
      (value "49R9")
      (footprint "RESC0603X28N")
      (description "Resistor - 1%")
      (fields
        (field (name "TOLERANCE") "±1%")
        (field (name "PART NUMBER") "R0201_49R9_1%_0.05W_200PPM")
        (field (name "POWER") "0.05W")
        (field (name "AUTHOR") "CERN DEM BC")
      )
      (libsource (lib "Resistors") (part "Resistor - 1%"))
    )
    (comp (ref "U1")
      (value "AFE5832ZBV")
      (footprint "BGA289C80P17X17_1500X1500X140")
      (fields
        (field (name "MANUFACTURER") "Texas Instruments")
        (field (name "SYMBOLCREATOR") "Altium")
        (field (name "PUBLISHER") "Texas Instruments")
      )
      (libsource (lib "TI_Pre_RTM") (part "AFE58JD32ZBV"))
    )
  )
  (nets
    (net (code "4") (name "/ADCCLK_N") (class "Default")
      (node (ref "C9") (pin "2") (pinfunction "2_2") (pintype "passive"))
      (node (ref "U1") (pin "J2") (pinfunction "ADC_CLKM_J2") (pintype "input"))
    )
    (net (code "5") (name "/ADCCLK_P") (class "Default")
      (node (ref "C5") (pin "2") (pinfunction "2_2") (pintype "passive"))
      (node (ref "U1") (pin "J1") (pinfunction "ADC_CLKP_J1") (pintype "input"))
    )
    (net (code "6") (name "/ADC_CLK_N") (class "Default")
      (node (ref "C9") (pin "1") (pinfunction "1_1") (pintype "passive"))
      (node (ref "R17") (pin "1") (pinfunction "1_1") (pintype "passive"))
    )
    (net (code "7") (name "/ADC_CLK_P") (class "Default")
      (node (ref "C5") (pin "1") (pinfunction "1_1") (pintype "passive"))
      (node (ref "R17") (pin "2") (pinfunction "2_2") (pintype "passive"))
    )
    (net (code "8") (name "/DCLK_N") (class "Default")
      (node (ref "U1") (pin "U9") (pinfunction "DCLKM_U9") (pintype "output"))
    )
    (net (code "9") (name "/DCLK_P") (class "Default")
      (node (ref "U1") (pin "T9") (pinfunction "DCLKP_T9") (pintype "output"))
    )
    (net (code "10") (name "/DOUT0_N") (class "Default")
      (node (ref "U1") (pin "T16") (pinfunction "DOUTM1_T16") (pintype "output"))
    )
    (net (code "11") (name "/DOUT0_P") (class "Default")
      (node (ref "U1") (pin "R16") (pinfunction "DOUTP1_R16") (pintype "output"))
    )
    (net (code "12") (name "/DOUT1_N") (class "Default")
      (node (ref "U1") (pin "T15") (pinfunction "DOUTM2_T15") (pintype "output"))
    )
    (net (code "13") (name "/DOUT1_P") (class "Default")
      (node (ref "U1") (pin "R15") (pinfunction "DOUTP2_R15") (pintype "output"))
    )
    (net (code "14") (name "/DOUT2_N") (class "Default")
      (node (ref "U1") (pin "T14") (pinfunction "DOUTM3_T14") (pintype "output"))
    )
    (net (code "15") (name "/DOUT2_P") (class "Default")
      (node (ref "U1") (pin "R14") (pinfunction "DOUTP3_R14") (pintype "output"))
    )
    (net (code "16") (name "/DOUT3_N") (class "Default")
      (node (ref "U1") (pin "U13") (pinfunction "DOUTM4_U13") (pintype "output"))
    )
    (net (code "17") (name "/DOUT3_P") (class "Default")
      (node (ref "U1") (pin "T13") (pinfunction "DOUTP4_T13") (pintype "output"))
    )
    (net (code "18") (name "/DOUT4_N") (class "Default")
      (node (ref "U1") (pin "U12") (pinfunction "DOUTM5_U12") (pintype "output"))
    )
    (net (code "19") (name "/DOUT4_P") (class "Default")
      (node (ref "U1") (pin "T12") (pinfunction "DOUTP5_T12") (pintype "output"))
    )
    (net (code "20") (name "/DOUT5_N") (class "Default")
      (node (ref "U1") (pin "R11") (pinfunction "DOUTM6_R11") (pintype "output"))
    )
    (net (code "21") (name "/DOUT5_P") (class "Default")
      (node (ref "U1") (pin "R12") (pinfunction "DOUTP6_R12") (pintype "output"))
    )
    (net (code "22") (name "/DOUT6_N") (class "Default")
      (node (ref "U1") (pin "U11") (pinfunction "DOUTM7_U11") (pintype "output"))
    )
    (net (code "23") (name "/DOUT6_P") (class "Default")
      (node (ref "U1") (pin "T11") (pinfunction "DOUTP7_T11") (pintype "output"))
    )
    (net (code "24") (name "/DOUT7_N") (class "Default")
      (node (ref "U1") (pin "U10") (pinfunction "DOUTM8_U10") (pintype "output"))
    )
    (net (code "25") (name "/DOUT7_P") (class "Default")
      (node (ref "U1") (pin "T10") (pinfunction "DOUTP8_T10") (pintype "output"))
    )
    (net (code "26") (name "/DOUT8_N") (class "Default")
      (node (ref "U1") (pin "U8") (pinfunction "DOUTM9_U8") (pintype "output"))
    )
    (net (code "27") (name "/DOUT8_P") (class "Default")
      (node (ref "U1") (pin "T8") (pinfunction "DOUTP9_T8") (pintype "output"))
    )
    (net (code "28") (name "/DOUT9_N") (class "Default")
      (node (ref "U1") (pin "U7") (pinfunction "DOUTM10_U7") (pintype "output"))
    )
    (net (code "29") (name "/DOUT9_P") (class "Default")
      (node (ref "U1") (pin "T7") (pinfunction "DOUTP10_T7") (pintype "output"))
    )
    (net (code "30") (name "/DOUT10_N") (class "Default")
      (node (ref "U1") (pin "R6") (pinfunction "DOUTM11_R6") (pintype "output"))
    )
    (net (code "31") (name "/DOUT10_P") (class "Default")
      (node (ref "U1") (pin "R7") (pinfunction "DOUTP11_R7") (pintype "output"))
    )
    (net (code "32") (name "/DOUT11_N") (class "Default")
      (node (ref "U1") (pin "U6") (pinfunction "DOUTM12_U6") (pintype "output"))
    )
    (net (code "33") (name "/DOUT11_P") (class "Default")
      (node (ref "U1") (pin "T6") (pinfunction "DOUTP12_T6") (pintype "output"))
    )
    (net (code "34") (name "/DOUT12_N") (class "Default")
      (node (ref "U1") (pin "U5") (pinfunction "DOUTM13_U5") (pintype "output"))
    )
    (net (code "35") (name "/DOUT12_P") (class "Default")
      (node (ref "U1") (pin "T5") (pinfunction "DOUTP13_T5") (pintype "output"))
    )
    (net (code "36") (name "/DOUT13_N") (class "Default")
      (node (ref "U1") (pin "T4") (pinfunction "DOUTM14_T4") (pintype "output"))
    )
    (net (code "37") (name "/DOUT13_P") (class "Default")
      (node (ref "U1") (pin "R4") (pinfunction "DOUTP14_R4") (pintype "output"))
    )
    (net (code "38") (name "/DOUT14_N") (class "Default")
      (node (ref "U1") (pin "T3") (pinfunction "DOUTM15_T3") (pintype "output"))
    )
    (net (code "39") (name "/DOUT14_P") (class "Default")
      (node (ref "U1") (pin "R3") (pinfunction "DOUTP15_R3") (pintype "output"))
    )
    (net (code "40") (name "/DOUT15_N") (class "Default")
      (node (ref "U1") (pin "T2") (pinfunction "DOUTM16_T2") (pintype "output"))
    )
    (net (code "41") (name "/DOUT15_P") (class "Default")
      (node (ref "U1") (pin "R2") (pinfunction "DOUTP16_R2") (pintype "output"))
    )
    (net (code "42") (name "/FCLK_N") (class "Default")
      (node (ref "U1") (pin "R8") (pinfunction "FCLKM_R8") (pintype "output"))
    )
    (net (code "43") (name "/FCLK_P") (class "Default")
      (node (ref "U1") (pin "R10") (pinfunction "FCLKP_R10") (pintype "output"))
    )
    (net (code "44") (name "/INP0") (class "Default")
      (node (ref "D2") (pin "6") (pinfunction "I/O4_6") (pintype "bidirectional"))
      (node (ref "R22") (pin "1") (pinfunction "1_1") (pintype "passive"))
      (node (ref "R24") (pin "1") (pinfunction "1_1") (pintype "passive"))
    )
    (net (code "45") (name "/INP1") (class "Default")
      (node (ref "D1") (pin "6") (pinfunction "I/O4_6") (pintype "bidirectional"))
      (node (ref "R26") (pin "2") (pinfunction "2_2") (pintype "passive"))
      (node (ref "R27") (pin "1") (pinfunction "1_1") (pintype "passive"))
    )
    (net (code "46") (name "/INP2") (class "Default")
      (node (ref "D2") (pin "1") (pinfunction "I/O1_1") (pintype "bidirectional"))
      (node (ref "R28") (pin "1") (pinfunction "1_1") (pintype "passive"))
      (node (ref "R29") (pin "1") (pinfunction "1_1") (pintype "passive"))
    )
    (net (code "47") (name "/INP3") (class "Default")
      (node (ref "D1") (pin "1") (pinfunction "I/O1_1") (pintype "bidirectional"))
      (node (ref "R30") (pin "2") (pinfunction "2_2") (pintype "passive"))
      (node (ref "R31") (pin "1") (pinfunction "1_1") (pintype "passive"))
    )
    (net (code "48") (name "/INP4") (class "Default")
      (node (ref "D2") (pin "4") (pinfunction "I/O3_4") (pintype "bidirectional"))
      (node (ref "R32") (pin "1") (pinfunction "1_1") (pintype "passive"))
      (node (ref "R33") (pin "1") (pinfunction "1_1") (pintype "passive"))
    )
    (net (code "49") (name "/INP5") (class "Default")
      (node (ref "D1") (pin "4") (pinfunction "I/O3_4") (pintype "bidirectional"))
      (node (ref "R34") (pin "2") (pinfunction "2_2") (pintype "passive"))
      (node (ref "R35") (pin "1") (pinfunction "1_1") (pintype "passive"))
    )
    (net (code "50") (name "/INP6") (class "Default")
      (node (ref "D2") (pin "3") (pinfunction "I/O2_3") (pintype "bidirectional"))
      (node (ref "R36") (pin "1") (pinfunction "1_1") (pintype "passive"))
      (node (ref "R37") (pin "1") (pinfunction "1_1") (pintype "passive"))
    )
    (net (code "51") (name "/INP7") (class "Default")
      (node (ref "D1") (pin "3") (pinfunction "I/O2_3") (pintype "bidirectional"))
      (node (ref "R38") (pin "2") (pinfunction "2_2") (pintype "passive"))
      (node (ref "R39") (pin "1") (pinfunction "1_1") (pintype "passive"))
    )
    (net (code "52") (name "/INP8") (class "Default")
      (node (ref "D4") (pin "6") (pinfunction "I/O4_6") (pintype "bidirectional"))
      (node (ref "R40") (pin "1") (pinfunction "1_1") (pintype "passive"))
      (node (ref "R41") (pin "1") (pinfunction "1_1") (pintype "passive"))
    )
    (net (code "53") (name "/INP9") (class "Default")
      (node (ref "D3") (pin "6") (pinfunction "I/O4_6") (pintype "bidirectional"))
      (node (ref "R42") (pin "2") (pinfunction "2_2") (pintype "passive"))
      (node (ref "R43") (pin "1") (pinfunction "1_1") (pintype "passive"))
    )
    (net (code "54") (name "/INP10") (class "Default")
      (node (ref "D4") (pin "1") (pinfunction "I/O1_1") (pintype "bidirectional"))
      (node (ref "R44") (pin "1") (pinfunction "1_1") (pintype "passive"))
      (node (ref "R45") (pin "1") (pinfunction "1_1") (pintype "passive"))
    )
    (net (code "55") (name "/INP11") (class "Default")
      (node (ref "D3") (pin "1") (pinfunction "I/O1_1") (pintype "bidirectional"))
      (node (ref "R46") (pin "2") (pinfunction "2_2") (pintype "passive"))
      (node (ref "R47") (pin "1") (pinfunction "1_1") (pintype "passive"))
    )
    (net (code "56") (name "/INP12") (class "Default")
      (node (ref "D4") (pin "4") (pinfunction "I/O3_4") (pintype "bidirectional"))
      (node (ref "R48") (pin "1") (pinfunction "1_1") (pintype "passive"))
      (node (ref "R49") (pin "1") (pinfunction "1_1") (pintype "passive"))
    )
    (net (code "57") (name "/INP13") (class "Default")
      (node (ref "D3") (pin "4") (pinfunction "I/O3_4") (pintype "bidirectional"))
      (node (ref "R50") (pin "2") (pinfunction "2_2") (pintype "passive"))
      (node (ref "R51") (pin "1") (pinfunction "1_1") (pintype "passive"))
    )
    (net (code "58") (name "/INP14") (class "Default")
      (node (ref "D4") (pin "3") (pinfunction "I/O2_3") (pintype "bidirectional"))
      (node (ref "R52") (pin "1") (pinfunction "1_1") (pintype "passive"))
      (node (ref "R53") (pin "1") (pinfunction "1_1") (pintype "passive"))
    )
    (net (code "59") (name "/INP15") (class "Default")
      (node (ref "D3") (pin "3") (pinfunction "I/O2_3") (pintype "bidirectional"))
      (node (ref "R54") (pin "2") (pinfunction "2_2") (pintype "passive"))
      (node (ref "R55") (pin "1") (pinfunction "1_1") (pintype "passive"))
    )
    (net (code "60") (name "/INP16") (class "Default")
      (node (ref "D6") (pin "6") (pinfunction "I/O4_6") (pintype "bidirectional"))
      (node (ref "R56") (pin "1") (pinfunction "1_1") (pintype "passive"))
      (node (ref "R57") (pin "1") (pinfunction "1_1") (pintype "passive"))
    )
    (net (code "61") (name "/INP17") (class "Default")
      (node (ref "D5") (pin "6") (pinfunction "I/O4_6") (pintype "bidirectional"))
      (node (ref "R58") (pin "2") (pinfunction "2_2") (pintype "passive"))
      (node (ref "R59") (pin "1") (pinfunction "1_1") (pintype "passive"))
    )
    (net (code "62") (name "/INP18") (class "Default")
      (node (ref "D6") (pin "1") (pinfunction "I/O1_1") (pintype "bidirectional"))
      (node (ref "R60") (pin "1") (pinfunction "1_1") (pintype "passive"))
      (node (ref "R61") (pin "1") (pinfunction "1_1") (pintype "passive"))
    )
    (net (code "63") (name "/INP19") (class "Default")
      (node (ref "D5") (pin "1") (pinfunction "I/O1_1") (pintype "bidirectional"))
      (node (ref "R62") (pin "2") (pinfunction "2_2") (pintype "passive"))
      (node (ref "R63") (pin "1") (pinfunction "1_1") (pintype "passive"))
    )
    (net (code "64") (name "/INP20") (class "Default")
      (node (ref "D6") (pin "4") (pinfunction "I/O3_4") (pintype "bidirectional"))
      (node (ref "R64") (pin "1") (pinfunction "1_1") (pintype "passive"))
      (node (ref "R65") (pin "1") (pinfunction "1_1") (pintype "passive"))
    )
    (net (code "65") (name "/INP21") (class "Default")
      (node (ref "D5") (pin "4") (pinfunction "I/O3_4") (pintype "bidirectional"))
      (node (ref "R66") (pin "2") (pinfunction "2_2") (pintype "passive"))
      (node (ref "R67") (pin "1") (pinfunction "1_1") (pintype "passive"))
    )
    (net (code "66") (name "/INP22") (class "Default")
      (node (ref "D6") (pin "3") (pinfunction "I/O2_3") (pintype "bidirectional"))
      (node (ref "R68") (pin "1") (pinfunction "1_1") (pintype "passive"))
      (node (ref "R69") (pin "1") (pinfunction "1_1") (pintype "passive"))
    )
    (net (code "67") (name "/INP23") (class "Default")
      (node (ref "D5") (pin "3") (pinfunction "I/O2_3") (pintype "bidirectional"))
      (node (ref "R70") (pin "2") (pinfunction "2_2") (pintype "passive"))
      (node (ref "R71") (pin "1") (pinfunction "1_1") (pintype "passive"))
    )
    (net (code "68") (name "/INP24") (class "Default")
      (node (ref "D8") (pin "6") (pinfunction "I/O4_6") (pintype "bidirectional"))
      (node (ref "R72") (pin "1") (pinfunction "1_1") (pintype "passive"))
      (node (ref "R73") (pin "1") (pinfunction "1_1") (pintype "passive"))
    )
    (net (code "69") (name "/INP25") (class "Default")
      (node (ref "D7") (pin "6") (pinfunction "I/O4_6") (pintype "bidirectional"))
      (node (ref "R74") (pin "2") (pinfunction "2_2") (pintype "passive"))
      (node (ref "R75") (pin "1") (pinfunction "1_1") (pintype "passive"))
    )
    (net (code "70") (name "/INP26") (class "Default")
      (node (ref "D8") (pin "1") (pinfunction "I/O1_1") (pintype "bidirectional"))
      (node (ref "R76") (pin "1") (pinfunction "1_1") (pintype "passive"))
      (node (ref "R77") (pin "1") (pinfunction "1_1") (pintype "passive"))
    )
    (net (code "71") (name "/INP27") (class "Default")
      (node (ref "D7") (pin "1") (pinfunction "I/O1_1") (pintype "bidirectional"))
      (node (ref "R78") (pin "2") (pinfunction "2_2") (pintype "passive"))
      (node (ref "R79") (pin "1") (pinfunction "1_1") (pintype "passive"))
    )
    (net (code "72") (name "/INP28") (class "Default")
      (node (ref "D8") (pin "4") (pinfunction "I/O3_4") (pintype "bidirectional"))
      (node (ref "R80") (pin "1") (pinfunction "1_1") (pintype "passive"))
      (node (ref "R81") (pin "1") (pinfunction "1_1") (pintype "passive"))
    )
    (net (code "73") (name "/INP29") (class "Default")
      (node (ref "D7") (pin "4") (pinfunction "I/O3_4") (pintype "bidirectional"))
      (node (ref "R82") (pin "2") (pinfunction "2_2") (pintype "passive"))
      (node (ref "R83") (pin "1") (pinfunction "1_1") (pintype "passive"))
    )
    (net (code "74") (name "/INP30") (class "Default")
      (node (ref "D8") (pin "3") (pinfunction "I/O2_3") (pintype "bidirectional"))
      (node (ref "R84") (pin "1") (pinfunction "1_1") (pintype "passive"))
      (node (ref "R85") (pin "1") (pinfunction "1_1") (pintype "passive"))
    )
    (net (code "75") (name "/INP31") (class "Default")
      (node (ref "D7") (pin "3") (pinfunction "I/O2_3") (pintype "bidirectional"))
      (node (ref "R86") (pin "2") (pinfunction "2_2") (pintype "passive"))
      (node (ref "R87") (pin "1") (pinfunction "1_1") (pintype "passive"))
    )
    (net (code "77") (name "/IN_N") (class "Default")
      (node (ref "C26") (pin "1") (pinfunction "1_1") (pintype "passive"))
      (node (ref "C27") (pin "1") (pinfunction "1_1") (pintype "passive"))
      (node (ref "C3") (pin "1") (pinfunction "1_1") (pintype "passive"))
      (node (ref "C4") (pin "1") (pinfunction "1_1") (pintype "passive"))
      (node (ref "C71") (pin "1") (pinfunction "1_1") (pintype "passive"))
      (node (ref "C72") (pin "1") (pinfunction "1_1") (pintype "passive"))
      (node (ref "C73") (pin "1") (pinfunction "1_1") (pintype "passive"))
      (node (ref "C74") (pin "1") (pinfunction "1_1") (pintype "passive"))
      (node (ref "R22") (pin "2") (pinfunction "2_2") (pintype "passive"))
      (node (ref "R27") (pin "2") (pinfunction "2_2") (pintype "passive"))
      (node (ref "R28") (pin "2") (pinfunction "2_2") (pintype "passive"))
      (node (ref "R31") (pin "2") (pinfunction "2_2") (pintype "passive"))
      (node (ref "R32") (pin "2") (pinfunction "2_2") (pintype "passive"))
      (node (ref "R35") (pin "2") (pinfunction "2_2") (pintype "passive"))
      (node (ref "R36") (pin "2") (pinfunction "2_2") (pintype "passive"))
      (node (ref "R39") (pin "2") (pinfunction "2_2") (pintype "passive"))
      (node (ref "R40") (pin "2") (pinfunction "2_2") (pintype "passive"))
      (node (ref "R43") (pin "2") (pinfunction "2_2") (pintype "passive"))
      (node (ref "R44") (pin "2") (pinfunction "2_2") (pintype "passive"))
      (node (ref "R47") (pin "2") (pinfunction "2_2") (pintype "passive"))
      (node (ref "R48") (pin "2") (pinfunction "2_2") (pintype "passive"))
      (node (ref "R51") (pin "2") (pinfunction "2_2") (pintype "passive"))
      (node (ref "R52") (pin "2") (pinfunction "2_2") (pintype "passive"))
      (node (ref "R55") (pin "2") (pinfunction "2_2") (pintype "passive"))
      (node (ref "R56") (pin "2") (pinfunction "2_2") (pintype "passive"))
      (node (ref "R59") (pin "2") (pinfunction "2_2") (pintype "passive"))
      (node (ref "R60") (pin "2") (pinfunction "2_2") (pintype "passive"))
      (node (ref "R63") (pin "2") (pinfunction "2_2") (pintype "passive"))
      (node (ref "R64") (pin "2") (pinfunction "2_2") (pintype "passive"))
      (node (ref "R67") (pin "2") (pinfunction "2_2") (pintype "passive"))
      (node (ref "R68") (pin "2") (pinfunction "2_2") (pintype "passive"))
      (node (ref "R71") (pin "2") (pinfunction "2_2") (pintype "passive"))
      (node (ref "R72") (pin "2") (pinfunction "2_2") (pintype "passive"))
      (node (ref "R75") (pin "2") (pinfunction "2_2") (pintype "passive"))
      (node (ref "R76") (pin "2") (pinfunction "2_2") (pintype "passive"))
      (node (ref "R79") (pin "2") (pinfunction "2_2") (pintype "passive"))
      (node (ref "R80") (pin "2") (pinfunction "2_2") (pintype "passive"))
      (node (ref "R83") (pin "2") (pinfunction "2_2") (pintype "passive"))
      (node (ref "R84") (pin "2") (pinfunction "2_2") (pintype "passive"))
      (node (ref "R87") (pin "2") (pinfunction "2_2") (pintype "passive"))
      (node (ref "U1") (pin "B1") (pinfunction "INM31_B1") (pintype "input"))
      (node (ref "U1") (pin "B10") (pinfunction "INM15_B10") (pintype "input"))
      (node (ref "U1") (pin "B11") (pinfunction "INM13_B11") (pintype "input"))
      (node (ref "U1") (pin "B12") (pinfunction "INM11_B12") (pintype "input"))
      (node (ref "U1") (pin "B13") (pinfunction "INM9_B13") (pintype "input"))
      (node (ref "U1") (pin "B14") (pinfunction "INM7_B14") (pintype "input"))
      (node (ref "U1") (pin "B15") (pinfunction "INM5_B15") (pintype "input"))
      (node (ref "U1") (pin "B16") (pinfunction "INM3_B16") (pintype "input"))
      (node (ref "U1") (pin "B17") (pinfunction "INM1_B17") (pintype "input"))
      (node (ref "U1") (pin "B2") (pinfunction "INM29_B2") (pintype "input"))
      (node (ref "U1") (pin "B3") (pinfunction "INM27_B3") (pintype "input"))
      (node (ref "U1") (pin "B4") (pinfunction "INM25_B4") (pintype "input"))
      (node (ref "U1") (pin "B5") (pinfunction "INM23_B5") (pintype "input"))
      (node (ref "U1") (pin "B6") (pinfunction "INM21_B6") (pintype "input"))
      (node (ref "U1") (pin "B7") (pinfunction "INM19_B7") (pintype "input"))
      (node (ref "U1") (pin "B8") (pinfunction "INM17_B8") (pintype "input"))
      (node (ref "U1") (pin "D1") (pinfunction "INM32_D1") (pintype "input"))
      (node (ref "U1") (pin "D10") (pinfunction "INM16_D10") (pintype "input"))
      (node (ref "U1") (pin "D11") (pinfunction "INM14_D11") (pintype "input"))
      (node (ref "U1") (pin "D12") (pinfunction "INM12_D12") (pintype "input"))
      (node (ref "U1") (pin "D13") (pinfunction "INM10_D13") (pintype "input"))
      (node (ref "U1") (pin "D14") (pinfunction "INM8_D14") (pintype "input"))
      (node (ref "U1") (pin "D15") (pinfunction "INM6_D15") (pintype "input"))
      (node (ref "U1") (pin "D16") (pinfunction "INM4_D16") (pintype "input"))
      (node (ref "U1") (pin "D17") (pinfunction "INM2_D17") (pintype "input"))
      (node (ref "U1") (pin "D2") (pinfunction "INM30_D2") (pintype "input"))
      (node (ref "U1") (pin "D3") (pinfunction "INM28_D3") (pintype "input"))
      (node (ref "U1") (pin "D4") (pinfunction "INM26_D4") (pintype "input"))
      (node (ref "U1") (pin "D5") (pinfunction "INM24_D5") (pintype "input"))
      (node (ref "U1") (pin "D6") (pinfunction "INM22_D6") (pintype "input"))
      (node (ref "U1") (pin "D7") (pinfunction "INM20_D7") (pintype "input"))
      (node (ref "U1") (pin "D8") (pinfunction "INM18_D8") (pintype "input"))
    )
    (net (code "78") (name "/PDN_GBL") (class "Default")
      (node (ref "U1") (pin "M16") (pinfunction "PDN_GBL_M16") (pintype "input"))
    )
    (net (code "79") (name "/RESET") (class "Default")
      (node (ref "U1") (pin "L17") (pinfunction "RESET_L17") (pintype "input"))
    )
    (net (code "80") (name "/SCLK") (class "Default")
      (node (ref "U1") (pin "J17") (pinfunction "SCLK_J17") (pintype "input"))
    )
    (net (code "81") (name "/SDIN") (class "Default")
      (node (ref "U1") (pin "L16") (pinfunction "SDIN_L16") (pintype "bidirectional"))
    )
    (net (code "82") (name "/SDOUT") (class "Default")
      (node (ref "U1") (pin "J16") (pinfunction "SDOUT_J16") (pintype "output"))
    )
    (net (code "83") (name "/SENE") (class "Default")
      (node (ref "U1") (pin "K17") (pinfunction "SENE_K17") (pintype "input"))
    )
    (net (code "84") (name "/SENO") (class "Default")
      (node (ref "U1") (pin "K15") (pinfunction "SENO_K15") (pintype "input"))
    )
    (net (code "85") (name "/TX_TRIG") (class "Default")
      (node (ref "U1") (pin "M15") (pinfunction "TX_TRIG_M15") (pintype "input"))
    )
    (net (code "89") (name "GND") (class "Default")
      (node (ref "C1") (pin "1") (pinfunction "1_1") (pintype "passive"))
      (node (ref "C14") (pin "1") (pinfunction "1_1") (pintype "passive"))
      (node (ref "C15") (pin "1") (pinfunction "1_1") (pintype "passive"))
      (node (ref "C2") (pin "1") (pinfunction "1_1") (pintype "passive"))
      (node (ref "C26") (pin "2") (pinfunction "2_2") (pintype "passive"))
      (node (ref "C27") (pin "2") (pinfunction "2_2") (pintype "passive"))
      (node (ref "C3") (pin "2") (pinfunction "2_2") (pintype "passive"))
      (node (ref "C33") (pin "1") (pinfunction "1_1") (pintype "passive"))
      (node (ref "C34") (pin "1") (pinfunction "1_1") (pintype "passive"))
      (node (ref "C35") (pin "1") (pinfunction "1_1") (pintype "passive"))
      (node (ref "C4") (pin "2") (pinfunction "2_2") (pintype "passive"))
      (node (ref "C57") (pin "2") (pinfunction "2_2") (pintype "passive"))
      (node (ref "C58") (pin "2") (pinfunction "2_2") (pintype "passive"))
      (node (ref "C59") (pin "2") (pinfunction "2_2") (pintype "passive"))
      (node (ref "C6") (pin "1") (pinfunction "1_1") (pintype "passive"))
      (node (ref "C60") (pin "2") (pinfunction "2_2") (pintype "passive"))
      (node (ref "C61") (pin "2") (pinfunction "2_2") (pintype "passive"))
      (node (ref "C62") (pin "2") (pinfunction "2_2") (pintype "passive"))
      (node (ref "C69") (pin "2") (pinfunction "2_2") (pintype "passive"))
      (node (ref "C70") (pin "2") (pinfunction "2_2") (pintype "passive"))
      (node (ref "C71") (pin "2") (pinfunction "2_2") (pintype "passive"))
      (node (ref "C72") (pin "2") (pinfunction "2_2") (pintype "passive"))
      (node (ref "C73") (pin "2") (pinfunction "2_2") (pintype "passive"))
      (node (ref "C74") (pin "2") (pinfunction "2_2") (pintype "passive"))
      (node (ref "D1") (pin "2") (pinfunction "GND_2") (pintype "power_in"))
      (node (ref "D2") (pin "2") (pinfunction "GND_2") (pintype "power_in"))
      (node (ref "D3") (pin "2") (pinfunction "GND_2") (pintype "power_in"))
      (node (ref "D4") (pin "2") (pinfunction "GND_2") (pintype "power_in"))
      (node (ref "D5") (pin "2") (pinfunction "GND_2") (pintype "power_in"))
      (node (ref "D6") (pin "2") (pinfunction "GND_2") (pintype "power_in"))
      (node (ref "D7") (pin "2") (pinfunction "GND_2") (pintype "power_in"))
      (node (ref "D8") (pin "2") (pinfunction "GND_2") (pintype "power_in"))
    )
    (net (code "90") (name "Net-(U1A-INP1)") (class "Default")
      (node (ref "R24") (pin "2") (pinfunction "2_2") (pintype "passive"))
      (node (ref "U1") (pin "A17") (pinfunction "INP1_A17") (pintype "input"))
    )
    (net (code "91") (name "Net-(U1A-INP2)") (class "Default")
      (node (ref "R26") (pin "1") (pinfunction "1_1") (pintype "passive"))
      (node (ref "U1") (pin "C17") (pinfunction "INP2_C17") (pintype "input"))
    )
    (net (code "92") (name "Net-(U1A-INP3)") (class "Default")
      (node (ref "R29") (pin "2") (pinfunction "2_2") (pintype "passive"))
      (node (ref "U1") (pin "A16") (pinfunction "INP3_A16") (pintype "input"))
    )
    (net (code "93") (name "Net-(U1A-INP4)") (class "Default")
      (node (ref "R30") (pin "1") (pinfunction "1_1") (pintype "passive"))
      (node (ref "U1") (pin "C16") (pinfunction "INP4_C16") (pintype "input"))
    )
    (net (code "94") (name "Net-(U1A-INP5)") (class "Default")
      (node (ref "R33") (pin "2") (pinfunction "2_2") (pintype "passive"))
      (node (ref "U1") (pin "A15") (pinfunction "INP5_A15") (pintype "input"))
    )
    (net (code "95") (name "Net-(U1A-INP6)") (class "Default")
      (node (ref "R34") (pin "1") (pinfunction "1_1") (pintype "passive"))
      (node (ref "U1") (pin "C15") (pinfunction "INP6_C15") (pintype "input"))
    )
    (net (code "96") (name "Net-(U1A-INP7)") (class "Default")
      (node (ref "R37") (pin "2") (pinfunction "2_2") (pintype "passive"))
      (node (ref "U1") (pin "A14") (pinfunction "INP7_A14") (pintype "input"))
    )
    (net (code "97") (name "Net-(U1A-INP8)") (class "Default")
      (node (ref "R38") (pin "1") (pinfunction "1_1") (pintype "passive"))
      (node (ref "U1") (pin "C14") (pinfunction "INP8_C14") (pintype "input"))
    )
    (net (code "98") (name "Net-(U1A-INP9)") (class "Default")
      (node (ref "R41") (pin "2") (pinfunction "2_2") (pintype "passive"))
      (node (ref "U1") (pin "A13") (pinfunction "INP9_A13") (pintype "input"))
    )
    (net (code "99") (name "Net-(U1A-INP10)") (class "Default")
      (node (ref "R42") (pin "1") (pinfunction "1_1") (pintype "passive"))
      (node (ref "U1") (pin "C13") (pinfunction "INP10_C13") (pintype "input"))
    )
    (net (code "100") (name "Net-(U1A-INP11)") (class "Default")
      (node (ref "R45") (pin "2") (pinfunction "2_2") (pintype "passive"))
      (node (ref "U1") (pin "A12") (pinfunction "INP11_A12") (pintype "input"))
    )
    (net (code "101") (name "Net-(U1A-INP12)") (class "Default")
      (node (ref "R46") (pin "1") (pinfunction "1_1") (pintype "passive"))
      (node (ref "U1") (pin "C12") (pinfunction "INP12_C12") (pintype "input"))
    )
    (net (code "102") (name "Net-(U1A-INP13)") (class "Default")
      (node (ref "R49") (pin "2") (pinfunction "2_2") (pintype "passive"))
      (node (ref "U1") (pin "A11") (pinfunction "INP13_A11") (pintype "input"))
    )
    (net (code "103") (name "Net-(U1A-INP14)") (class "Default")
      (node (ref "R50") (pin "1") (pinfunction "1_1") (pintype "passive"))
      (node (ref "U1") (pin "C11") (pinfunction "INP14_C11") (pintype "input"))
    )
    (net (code "104") (name "Net-(U1A-INP15)") (class "Default")
      (node (ref "R53") (pin "2") (pinfunction "2_2") (pintype "passive"))
      (node (ref "U1") (pin "A10") (pinfunction "INP15_A10") (pintype "input"))
    )
    (net (code "105") (name "Net-(U1A-INP16)") (class "Default")
      (node (ref "R54") (pin "1") (pinfunction "1_1") (pintype "passive"))
      (node (ref "U1") (pin "C10") (pinfunction "INP16_C10") (pintype "input"))
    )
    (net (code "106") (name "Net-(U1A-INP17)") (class "Default")
      (node (ref "R57") (pin "2") (pinfunction "2_2") (pintype "passive"))
      (node (ref "U1") (pin "A8") (pinfunction "INP17_A8") (pintype "input"))
    )
    (net (code "107") (name "Net-(U1A-INP18)") (class "Default")
      (node (ref "R58") (pin "1") (pinfunction "1_1") (pintype "passive"))
      (node (ref "U1") (pin "C8") (pinfunction "INP18_C8") (pintype "input"))
    )
    (net (code "108") (name "Net-(U1A-INP19)") (class "Default")
      (node (ref "R61") (pin "2") (pinfunction "2_2") (pintype "passive"))
      (node (ref "U1") (pin "A7") (pinfunction "INP19_A7") (pintype "input"))
    )
    (net (code "109") (name "Net-(U1A-INP20)") (class "Default")
      (node (ref "R62") (pin "1") (pinfunction "1_1") (pintype "passive"))
      (node (ref "U1") (pin "C7") (pinfunction "INP20_C7") (pintype "input"))
    )
    (net (code "110") (name "Net-(U1A-INP21)") (class "Default")
      (node (ref "R65") (pin "2") (pinfunction "2_2") (pintype "passive"))
      (node (ref "U1") (pin "A6") (pinfunction "INP21_A6") (pintype "input"))
    )
    (net (code "111") (name "Net-(U1A-INP22)") (class "Default")
      (node (ref "R66") (pin "1") (pinfunction "1_1") (pintype "passive"))
      (node (ref "U1") (pin "C6") (pinfunction "INP22_C6") (pintype "input"))
    )
    (net (code "112") (name "Net-(U1A-INP23)") (class "Default")
      (node (ref "R69") (pin "2") (pinfunction "2_2") (pintype "passive"))
      (node (ref "U1") (pin "A5") (pinfunction "INP23_A5") (pintype "input"))
    )
    (net (code "113") (name "Net-(U1A-INP24)") (class "Default")
      (node (ref "R70") (pin "1") (pinfunction "1_1") (pintype "passive"))
      (node (ref "U1") (pin "C5") (pinfunction "INP24_C5") (pintype "input"))
    )
    (net (code "114") (name "Net-(U1A-INP25)") (class "Default")
      (node (ref "R73") (pin "2") (pinfunction "2_2") (pintype "passive"))
      (node (ref "U1") (pin "A4") (pinfunction "INP25_A4") (pintype "input"))
    )
    (net (code "115") (name "Net-(U1A-INP26)") (class "Default")
      (node (ref "R74") (pin "1") (pinfunction "1_1") (pintype "passive"))
      (node (ref "U1") (pin "C4") (pinfunction "INP26_C4") (pintype "input"))
    )
    (net (code "116") (name "Net-(U1A-INP27)") (class "Default")
      (node (ref "R77") (pin "2") (pinfunction "2_2") (pintype "passive"))
      (node (ref "U1") (pin "A3") (pinfunction "INP27_A3") (pintype "input"))
    )
    (net (code "117") (name "Net-(U1A-INP28)") (class "Default")
      (node (ref "R78") (pin "1") (pinfunction "1_1") (pintype "passive"))
      (node (ref "U1") (pin "C3") (pinfunction "INP28_C3") (pintype "input"))
    )
    (net (code "118") (name "Net-(U1A-INP29)") (class "Default")
      (node (ref "R81") (pin "2") (pinfunction "2_2") (pintype "passive"))
      (node (ref "U1") (pin "A2") (pinfunction "INP29_A2") (pintype "input"))
    )
    (net (code "119") (name "Net-(U1A-INP30)") (class "Default")
      (node (ref "R82") (pin "1") (pinfunction "1_1") (pintype "passive"))
      (node (ref "U1") (pin "C2") (pinfunction "INP30_C2") (pintype "input"))
    )
    (net (code "120") (name "Net-(U1A-INP31)") (class "Default")
      (node (ref "R85") (pin "2") (pinfunction "2_2") (pintype "passive"))
      (node (ref "U1") (pin "A1") (pinfunction "INP31_A1") (pintype "input"))
    )
    (net (code "121") (name "Net-(U1A-INP32)") (class "Default")
      (node (ref "R86") (pin "1") (pinfunction "1_1") (pintype "passive"))
      (node (ref "U1") (pin "C1") (pinfunction "INP32_C1") (pintype "input"))
    )
    (net (code "122") (name "Net-(U1E-CLKM_1X)") (class "Default")
      (node (ref "B13") (pin "1") (pinfunction "1_1") (pintype "bidirectional"))
      (node (ref "U1") (pin "H16") (pinfunction "CLKM_1X_H16") (pintype "input"))
    )
    (net (code "123") (name "Net-(U1E-CLKM_16X)") (class "Default")
      (node (ref "B11") (pin "1") (pinfunction "1_1") (pintype "bidirectional"))
      (node (ref "U1") (pin "F17") (pinfunction "CLKM_16X_F17") (pintype "input"))
    )
    (net (code "124") (name "Net-(U1E-CLKP_1X)") (class "Default")
      (node (ref "B12") (pin "1") (pinfunction "1_1") (pintype "bidirectional"))
      (node (ref "U1") (pin "H17") (pinfunction "CLKP_1X_H17") (pintype "input"))
    )
    (net (code "125") (name "Net-(U1E-CLKP_16X)") (class "Default")
      (node (ref "B10") (pin "1") (pinfunction "1_1") (pintype "bidirectional"))
      (node (ref "U1") (pin "F16") (pinfunction "CLKP_16X_F16") (pintype "input"))
    )
    (net (code "126") (name "Net-(U1H-BAND__GAPE)") (class "Default")
      (node (ref "C15") (pin "2") (pinfunction "2_2") (pintype "passive"))
      (node (ref "U1") (pin "G4") (pinfunction "BAND__GAPE_G4") (pintype "passive"))
    )
    (net (code "127") (name "Net-(U1H-BAND__GAPO)") (class "Default")
      (node (ref "C33") (pin "2") (pinfunction "2_2") (pintype "passive"))
      (node (ref "U1") (pin "G5") (pinfunction "BAND__GAPO_G5") (pintype "passive"))
    )
    (net (code "128") (name "Net-(U1H-BIAS__2P5E)") (class "Default")
      (node (ref "C6") (pin "2") (pinfunction "2_2") (pintype "passive"))
      (node (ref "U1") (pin "D9") (pinfunction "BIAS__2P5E_D9") (pintype "passive"))
    )
    (net (code "129") (name "Net-(U1H-BIAS__2P5O)") (class "Default")
      (node (ref "C14") (pin "2") (pinfunction "2_2") (pintype "passive"))
      (node (ref "U1") (pin "A9") (pinfunction "BIAS__2P5O_A9") (pintype "passive"))
    )
    (net (code "130") (name "Net-(U1H-LNA_IN__CME)") (class "Default")
      (node (ref "C34") (pin "2") (pinfunction "2_2") (pintype "passive"))
      (node (ref "U1") (pin "E4") (pinfunction "LNA_IN__CME_E4") (pintype "passive"))
    )
    (net (code "131") (name "Net-(U1H-LNA_IN__CMO)") (class "Default")
      (node (ref "C35") (pin "2") (pinfunction "2_2") (pintype "passive"))
      (node (ref "U1") (pin "E5") (pinfunction "LNA_IN__CMO_E5") (pintype "passive"))
    )
    (net (code "132") (name "Net-(U1H-SRC__BIASE)") (class "Default")
      (node (ref "C2") (pin "2") (pinfunction "2_2") (pintype "passive"))
      (node (ref "U1") (pin "E14") (pinfunction "SRC__BIASE_E14") (pintype "input"))
    )
    (net (code "133") (name "Net-(U1H-SRC__BIASO)") (class "Default")
      (node (ref "C1") (pin "2") (pinfunction "2_2") (pintype "passive"))
      (node (ref "U1") (pin "E13") (pinfunction "SRC__BIASO_E13") (pintype "input"))
    )
    (net (code "134") (name "Net-(U1H-TGC_PROF<1>)") (class "Default")
      (node (ref "B6") (pin "1") (pinfunction "1_1") (pintype "bidirectional"))
      (node (ref "U1") (pin "J5") (pinfunction "TGC_PROF<1>_J5") (pintype "input"))
    )
    (net (code "135") (name "Net-(U1H-TGC_PROF<2>)") (class "Default")
      (node (ref "B7") (pin "1") (pinfunction "1_1") (pintype "bidirectional"))
      (node (ref "U1") (pin "H5") (pinfunction "TGC_PROF<2>_H5") (pintype "input"))
    )
    (net (code "136") (name "Net-(U1H-TGC_SLOPE)") (class "Default")
      (node (ref "B8") (pin "1") (pinfunction "1_1") (pintype "bidirectional"))
      (node (ref "U1") (pin "H4") (pinfunction "TGC_SLOPE_H4") (pintype "input"))
    )
    (net (code "137") (name "Net-(U1H-TGC_UP_DN)") (class "Default")
      (node (ref "B9") (pin "1") (pinfunction "1_1") (pintype "bidirectional"))
      (node (ref "U1") (pin "J4") (pinfunction "TGC_UP_DN_J4") (pintype "input"))
    )
    (net (code "138") (name "Net-(U1H-TR_EN<1>)") (class "Default")
      (node (ref "B15") (pin "1") (pinfunction "1_1") (pintype "bidirectional"))
      (node (ref "U1") (pin "H14") (pinfunction "TR_EN<2>_H14") (pintype "input"))
      (node (ref "U1") (pin "H15") (pinfunction "TR_EN<3>_H15") (pintype "input"))
      (node (ref "U1") (pin "J14") (pinfunction "TR_EN<1>_J14") (pintype "input"))
      (node (ref "U1") (pin "J15") (pinfunction "TR_EN<4>_J15") (pintype "input"))
    )
    (net (code "139") (name "P1V8") (class "Default")
      (node (ref "U1") (pin "K16") (pinfunction "SPI_DIG_EN_K16") (pintype "passive"))
    )
    (net (code "140") (name "V_PROT") (class "Default")
      (node (ref "C57") (pin "1") (pinfunction "1_1") (pintype "passive"))
      (node (ref "C58") (pin "1") (pinfunction "1_1") (pintype "passive"))
      (node (ref "C59") (pin "1") (pinfunction "1_1") (pintype "passive"))
      (node (ref "C60") (pin "1") (pinfunction "1_1") (pintype "passive"))
      (node (ref "C61") (pin "1") (pinfunction "1_1") (pintype "passive"))
      (node (ref "C62") (pin "1") (pinfunction "1_1") (pintype "passive"))
      (node (ref "C69") (pin "1") (pinfunction "1_1") (pintype "passive"))
      (node (ref "C70") (pin "1") (pinfunction "1_1") (pintype "passive"))
      (node (ref "D1") (pin "5") (pinfunction "VBUS_5") (pintype "power_in"))
      (node (ref "D2") (pin "5") (pinfunction "VBUS_5") (pintype "power_in"))
      (node (ref "D3") (pin "5") (pinfunction "VBUS_5") (pintype "power_in"))
      (node (ref "D4") (pin "5") (pinfunction "VBUS_5") (pintype "power_in"))
      (node (ref "D5") (pin "5") (pinfunction "VBUS_5") (pintype "power_in"))
      (node (ref "D6") (pin "5") (pinfunction "VBUS_5") (pintype "power_in"))
      (node (ref "D7") (pin "5") (pinfunction "VBUS_5") (pintype "power_in"))
      (node (ref "D8") (pin "5") (pinfunction "VBUS_5") (pintype "power_in"))
    )
    (net (code "141") (name "unconnected-(U1C-CML1_OUTM-PadP17)") (class "Default")
      (node (ref "U1") (pin "P17") (pinfunction "CML1_OUTM_P17") (pintype "passive+no_connect"))
    )
    (net (code "142") (name "unconnected-(U1C-CML1_OUTP-PadN17)") (class "Default")
      (node (ref "U1") (pin "N17") (pinfunction "CML1_OUTP_N17") (pintype "passive+no_connect"))
    )
    (net (code "143") (name "unconnected-(U1C-CML2_OUTM-PadT17)") (class "Default")
      (node (ref "U1") (pin "T17") (pinfunction "CML2_OUTM_T17") (pintype "passive+no_connect"))
    )
    (net (code "144") (name "unconnected-(U1C-CML2_OUTP-PadR17)") (class "Default")
      (node (ref "U1") (pin "R17") (pinfunction "CML2_OUTP_R17") (pintype "passive+no_connect"))
    )
    (net (code "145") (name "unconnected-(U1C-CML3_OUTM-PadU16)") (class "Default")
      (node (ref "U1") (pin "U16") (pinfunction "CML3_OUTM_U16") (pintype "open_collector+no_connect"))
    )
    (net (code "146") (name "unconnected-(U1C-CML3_OUTP-PadU17)") (class "Default")
      (node (ref "U1") (pin "U17") (pinfunction "CML3_OUTP_U17") (pintype "open_collector+no_connect"))
    )
    (net (code "147") (name "unconnected-(U1C-CML4_OUTM-PadU14)") (class "Default")
      (node (ref "U1") (pin "U14") (pinfunction "CML4_OUTM_U14") (pintype "open_collector+no_connect"))
    )
    (net (code "148") (name "unconnected-(U1C-CML4_OUTP-PadU15)") (class "Default")
      (node (ref "U1") (pin "U15") (pinfunction "CML4_OUTP_U15") (pintype "open_collector+no_connect"))
    )
    (net (code "149") (name "unconnected-(U1C-CML5_OUTM-PadP1)") (class "Default")
      (node (ref "U1") (pin "P1") (pinfunction "CML5_OUTM_P1") (pintype "open_collector+no_connect"))
    )
    (net (code "150") (name "unconnected-(U1C-CML5_OUTP-PadN1)") (class "Default")
      (node (ref "U1") (pin "N1") (pinfunction "CML5_OUTP_N1") (pintype "open_collector+no_connect"))
    )
    (net (code "151") (name "unconnected-(U1C-CML6_OUTM-PadT1)") (class "Default")
      (node (ref "U1") (pin "T1") (pinfunction "CML6_OUTM_T1") (pintype "open_collector+no_connect"))
    )
    (net (code "152") (name "unconnected-(U1C-CML6_OUTP-PadR1)") (class "Default")
      (node (ref "U1") (pin "R1") (pinfunction "CML6_OUTP_R1") (pintype "open_collector+no_connect"))
    )
    (net (code "153") (name "unconnected-(U1C-CML7_OUTM-PadU2)") (class "Default")
      (node (ref "U1") (pin "U2") (pinfunction "CML7_OUTM_U2") (pintype "open_collector+no_connect"))
    )
    (net (code "154") (name "unconnected-(U1C-CML7_OUTP-PadU1)") (class "Default")
      (node (ref "U1") (pin "U1") (pinfunction "CML7_OUTP_U1") (pintype "open_collector+no_connect"))
    )
    (net (code "155") (name "unconnected-(U1C-CML8_OUTM-PadU4)") (class "Default")
      (node (ref "U1") (pin "U4") (pinfunction "CML8_OUTM_U4") (pintype "open_collector+no_connect"))
    )
    (net (code "156") (name "unconnected-(U1C-CML8_OUTP-PadU3)") (class "Default")
      (node (ref "U1") (pin "U3") (pinfunction "CML8_OUTP_U3") (pintype "open_collector+no_connect"))
    )
    (net (code "157") (name "unconnected-(U1F-PDN_FAST-PadM17)") (class "Default")
      (node (ref "U1") (pin "M17") (pinfunction "PDN_FAST_M17") (pintype "input+no_connect"))
    )
    (net (code "158") (name "unconnected-(U1G-SYNCM_SERDES-PadL2)") (class "Default")
      (node (ref "U1") (pin "L2") (pinfunction "SYNCM_SERDES_L2") (pintype "passive+no_connect"))
    )
    (net (code "159") (name "unconnected-(U1G-SYNCP_SERDES-PadL1)") (class "Default")
      (node (ref "U1") (pin "L1") (pinfunction "SYNCP_SERDES_L1") (pintype "passive+no_connect"))
    )
    (net (code "160") (name "unconnected-(U1G-SYSREFM_SERDES-PadM2)") (class "Default")
      (node (ref "U1") (pin "M2") (pinfunction "SYSREFM_SERDES_M2") (pintype "passive+no_connect"))
    )
    (net (code "161") (name "unconnected-(U1G-SYSREFP_SERDES-PadM1)") (class "Default")
      (node (ref "U1") (pin "M1") (pinfunction "SYSREFP_SERDES_M1") (pintype "passive+no_connect"))
    )
    (net (code "162") (name "unconnected-(U1I-CW_IP_OUTM-PadF2)") (class "Default")
      (node (ref "U1") (pin "F2") (pinfunction "CW_IP_OUTM_F2") (pintype "output+no_connect"))
    )
    (net (code "163") (name "unconnected-(U1I-CW_IP_OUTP-PadF1)") (class "Default")
      (node (ref "U1") (pin "F1") (pinfunction "CW_IP_OUTP_F1") (pintype "output+no_connect"))
    )
    (net (code "164") (name "unconnected-(U1I-CW_QP_OUTM-PadG2)") (class "Default")
      (node (ref "U1") (pin "G2") (pinfunction "CW_QP_OUTM_G2") (pintype "output+no_connect"))
    )
    (net (code "165") (name "unconnected-(U1I-CW_QP_OUTP-PadG1)") (class "Default")
      (node (ref "U1") (pin "G1") (pinfunction "CW_QP_OUTP_G1") (pintype "output+no_connect"))
    )
  )
)
